# homeboard29.net
KiCad netlist of a schematic drawn in EAGLE
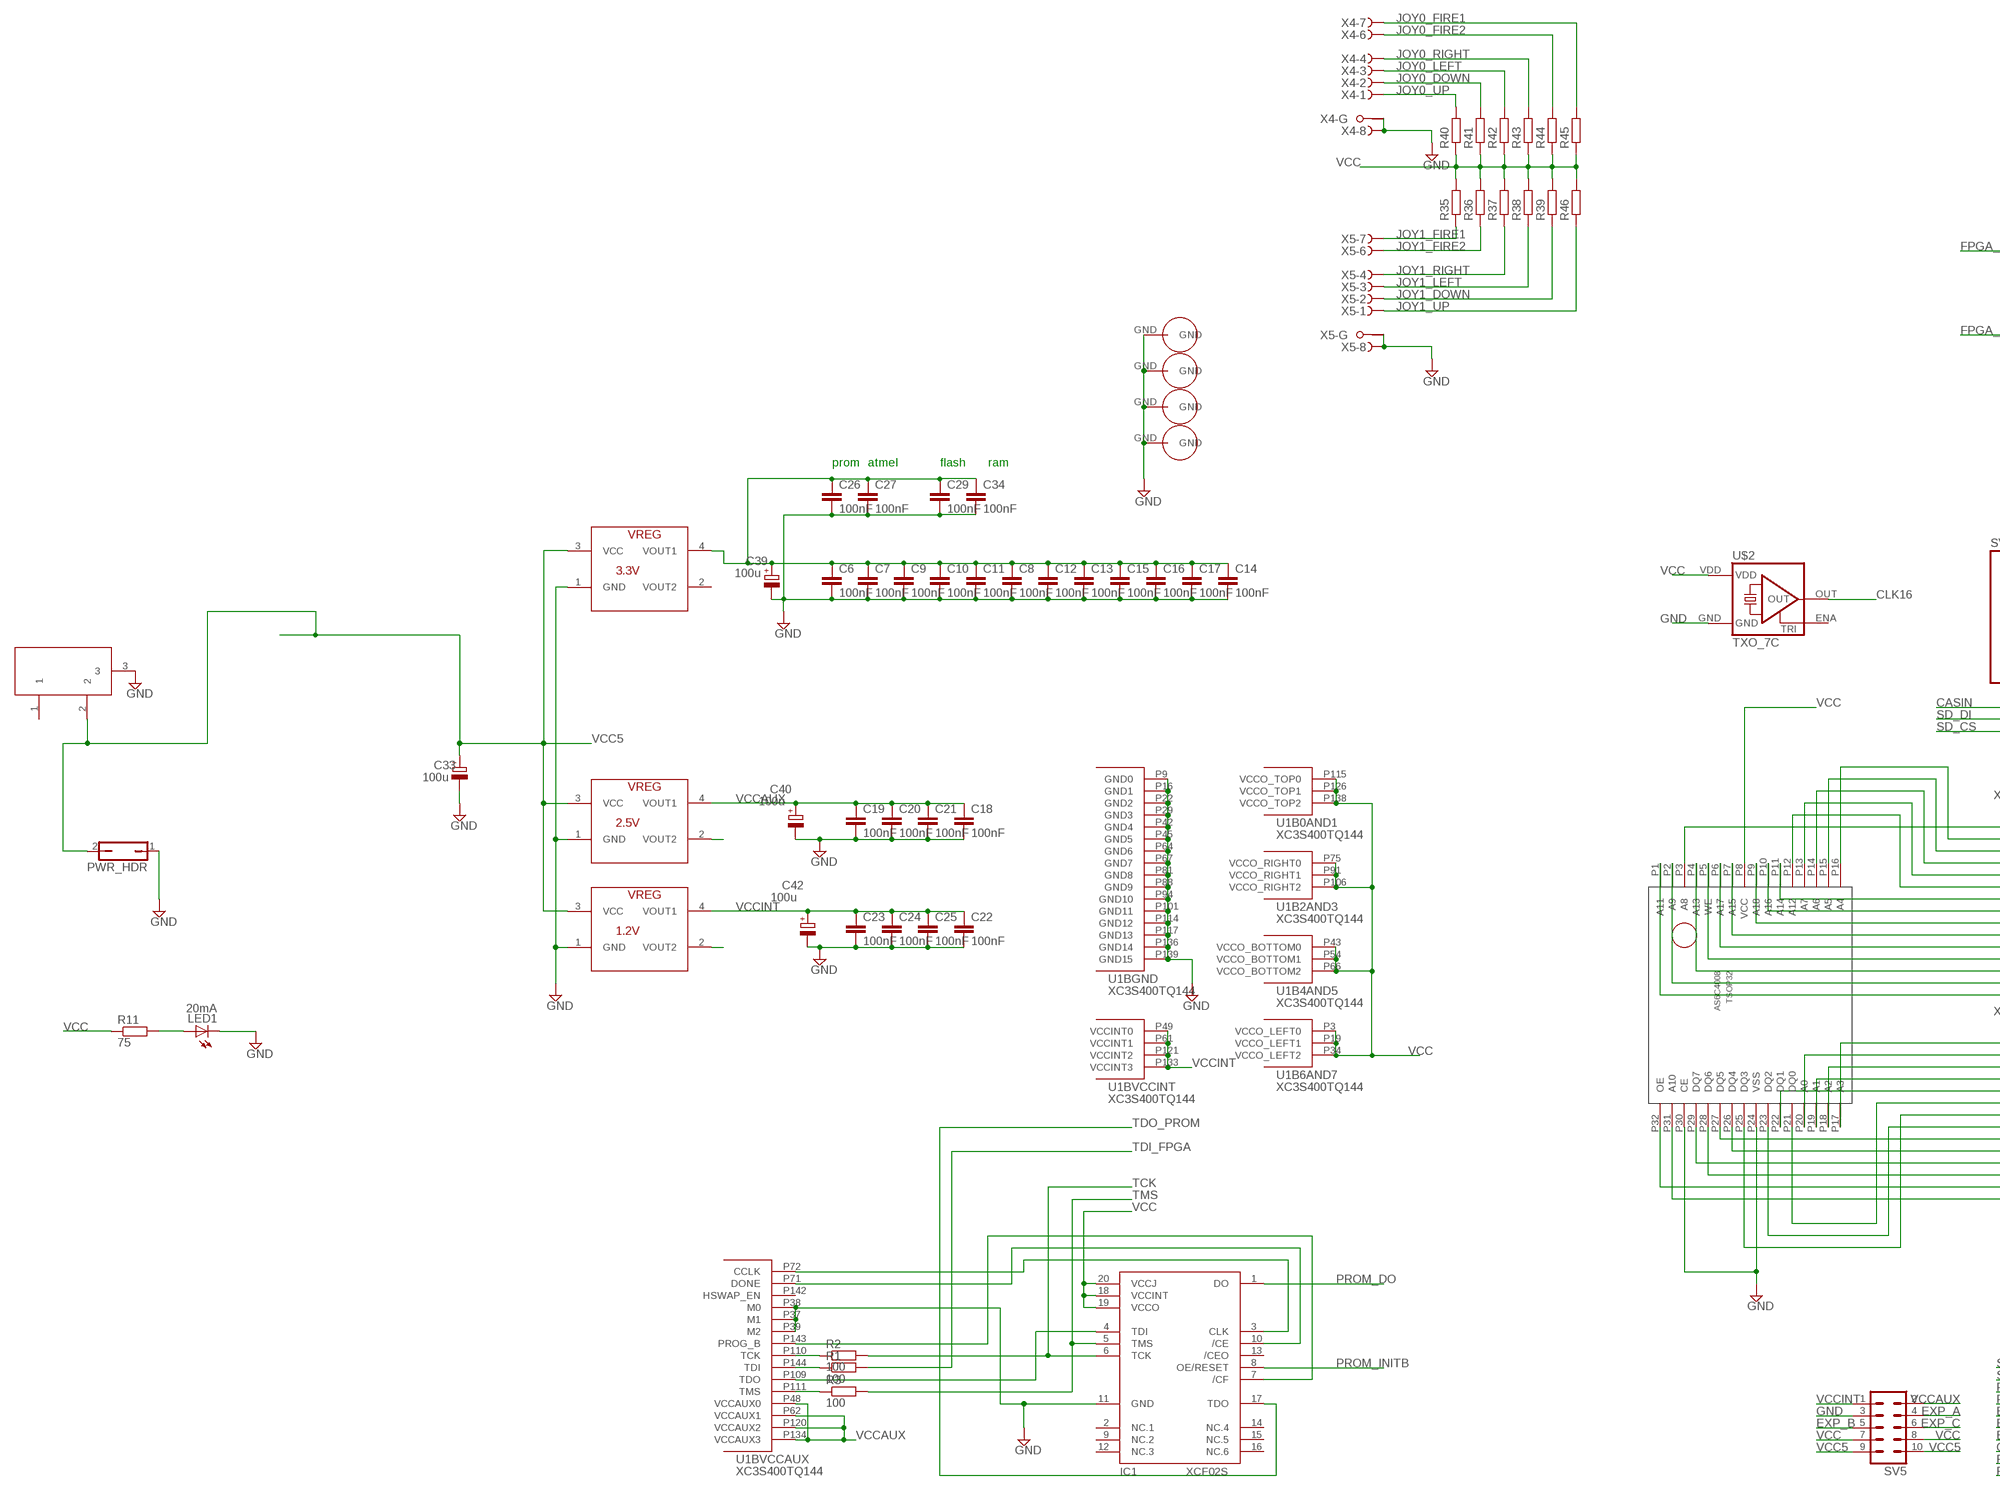
[diagram p0: schematic, sheet 1, part 1 of 3]
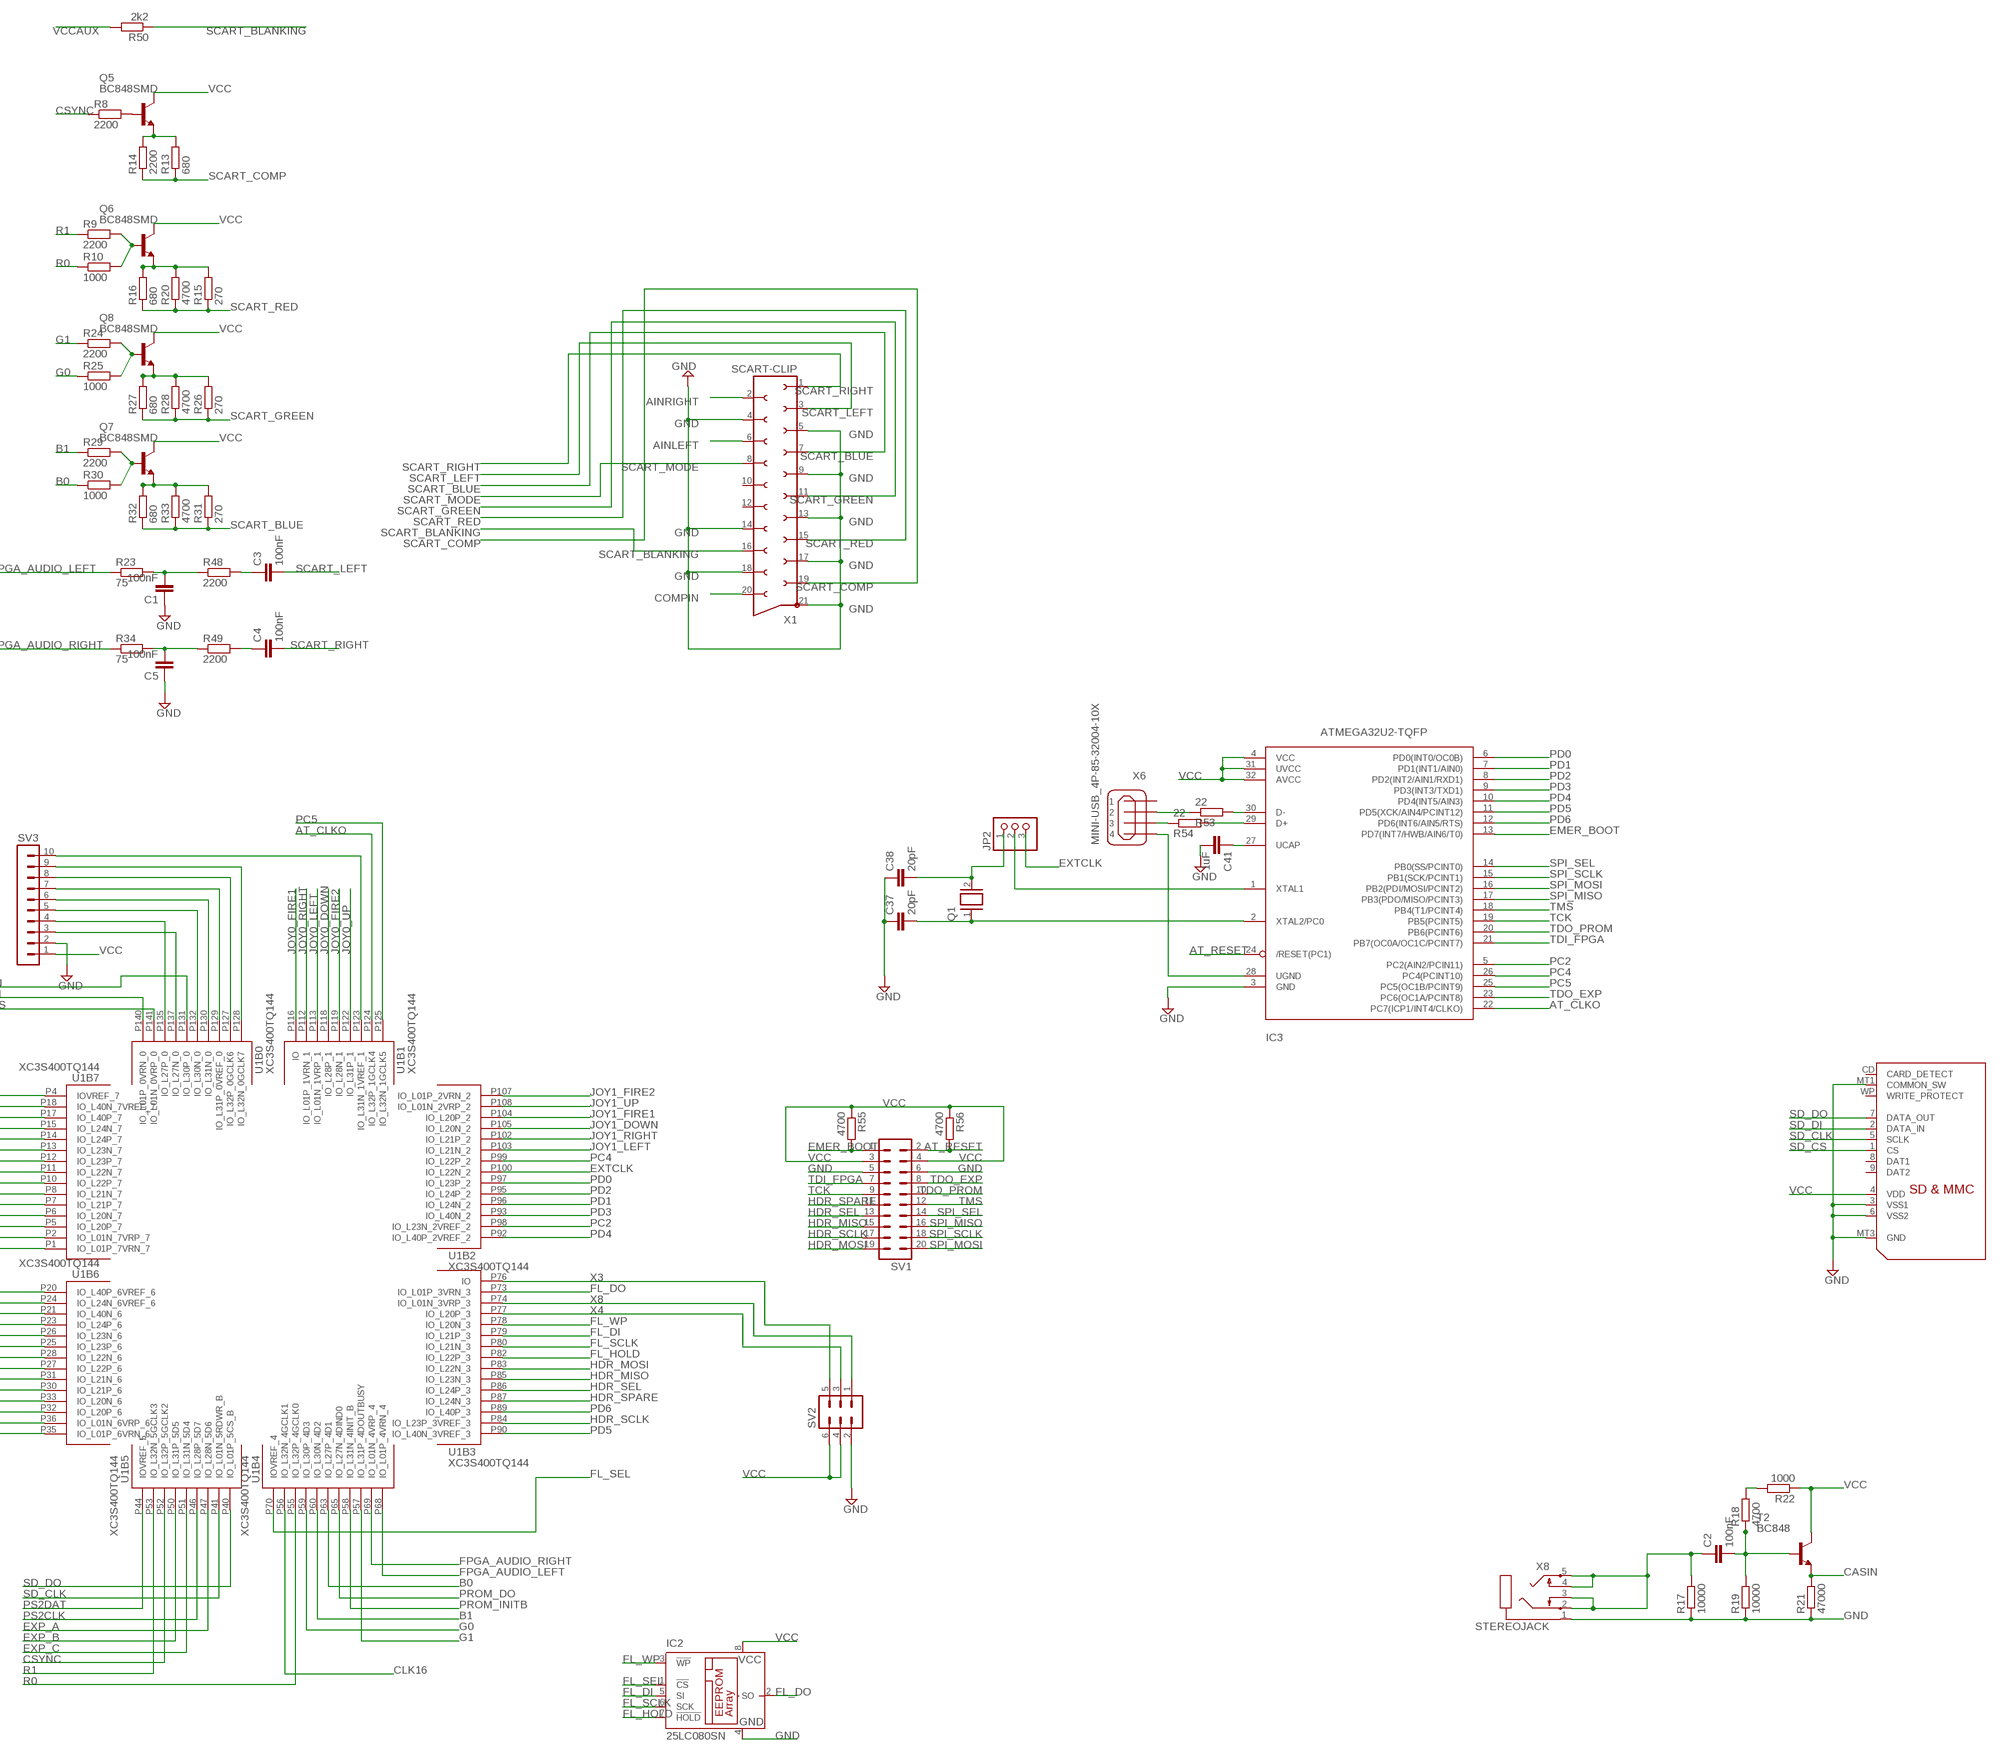
[diagram p1: schematic, sheet 1, part 2 of 3]
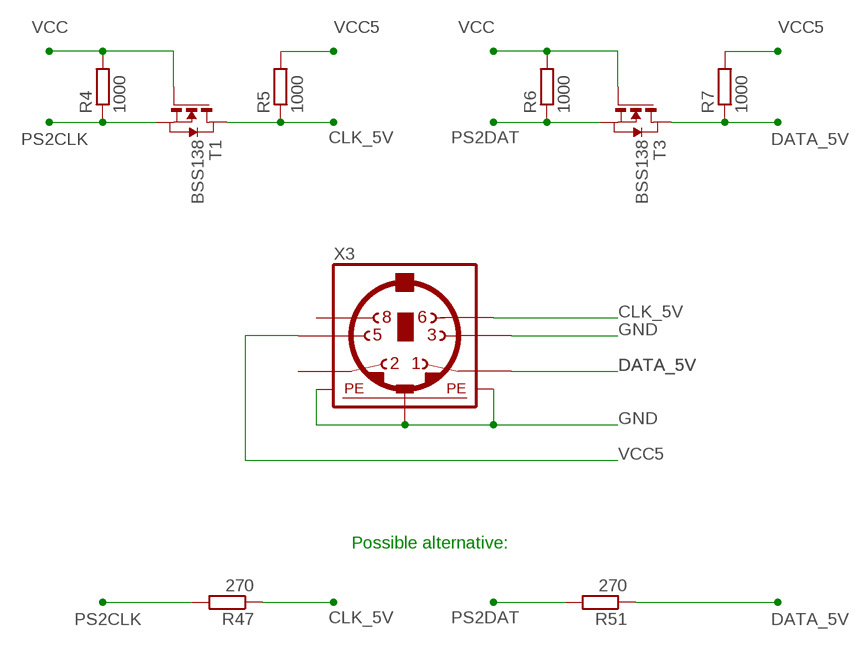
[diagram p2: schematic, sheet 1, part 3 of 3]

(export (version "E")
  (design (tool "Eeschema 10.0.6"))
  (components
    (comp (ref "C1")
      (value "100nF")
      (footprint "eagle-import:C0603")
      (libsource (lib "eagle-import") (part "resistor_C-EUC0603"))
    )
    (comp (ref "C2")
      (value "100nF")
      (footprint "eagle-import:C0603")
      (libsource (lib "eagle-import") (part "resistor_C-EUC0603"))
    )
    (comp (ref "C3")
      (value "100nF")
      (footprint "eagle-import:C0603")
      (libsource (lib "eagle-import") (part "resistor_C-EUC0603"))
    )
    (comp (ref "C4")
      (value "100nF")
      (footprint "eagle-import:C0603")
      (libsource (lib "eagle-import") (part "resistor_C-EUC0603"))
    )
    (comp (ref "C5")
      (value "100nF")
      (footprint "eagle-import:C0603")
      (libsource (lib "eagle-import") (part "resistor_C-EUC0603"))
    )
    (comp (ref "C6")
      (value "100nF")
      (footprint "eagle-import:C0603")
      (libsource (lib "eagle-import") (part "C-EUC0603"))
    )
    (comp (ref "C7")
      (value "100nF")
      (footprint "eagle-import:C0603")
      (libsource (lib "eagle-import") (part "C-EUC0603"))
    )
    (comp (ref "C8")
      (value "100nF")
      (footprint "eagle-import:C0603")
      (libsource (lib "eagle-import") (part "C-EUC0603"))
    )
    (comp (ref "C9")
      (value "100nF")
      (footprint "eagle-import:C0603")
      (libsource (lib "eagle-import") (part "C-EUC0603"))
    )
    (comp (ref "C10")
      (value "100nF")
      (footprint "eagle-import:C0603")
      (libsource (lib "eagle-import") (part "C-EUC0603"))
    )
    (comp (ref "C11")
      (value "100nF")
      (footprint "eagle-import:C0603")
      (libsource (lib "eagle-import") (part "C-EUC0603"))
    )
    (comp (ref "C12")
      (value "100nF")
      (footprint "eagle-import:C0603")
      (libsource (lib "eagle-import") (part "C-EUC0603"))
    )
    (comp (ref "C13")
      (value "100nF")
      (footprint "eagle-import:C0603")
      (libsource (lib "eagle-import") (part "C-EUC0603"))
    )
    (comp (ref "C14")
      (value "100nF")
      (footprint "eagle-import:C0603")
      (libsource (lib "eagle-import") (part "C-EUC0603"))
    )
    (comp (ref "C15")
      (value "100nF")
      (footprint "eagle-import:C0603")
      (libsource (lib "eagle-import") (part "C-EUC0603"))
    )
    (comp (ref "C16")
      (value "100nF")
      (footprint "eagle-import:C0603")
      (libsource (lib "eagle-import") (part "C-EUC0603"))
    )
    (comp (ref "C17")
      (value "100nF")
      (footprint "eagle-import:C0603")
      (libsource (lib "eagle-import") (part "C-EUC0603"))
    )
    (comp (ref "C18")
      (value "100nF")
      (footprint "eagle-import:C0603")
      (libsource (lib "eagle-import") (part "C-EUC0603"))
    )
    (comp (ref "C19")
      (value "100nF")
      (footprint "eagle-import:C0603")
      (libsource (lib "eagle-import") (part "C-EUC0603"))
    )
    (comp (ref "C20")
      (value "100nF")
      (footprint "eagle-import:C0603")
      (libsource (lib "eagle-import") (part "C-EUC0603"))
    )
    (comp (ref "C21")
      (value "100nF")
      (footprint "eagle-import:C0603")
      (libsource (lib "eagle-import") (part "C-EUC0603"))
    )
    (comp (ref "C22")
      (value "100nF")
      (footprint "eagle-import:C0603")
      (libsource (lib "eagle-import") (part "C-EUC0603"))
    )
    (comp (ref "C23")
      (value "100nF")
      (footprint "eagle-import:C0603")
      (libsource (lib "eagle-import") (part "C-EUC0603"))
    )
    (comp (ref "C24")
      (value "100nF")
      (footprint "eagle-import:C0603")
      (libsource (lib "eagle-import") (part "C-EUC0603"))
    )
    (comp (ref "C25")
      (value "100nF")
      (footprint "eagle-import:C0603")
      (libsource (lib "eagle-import") (part "C-EUC0603"))
    )
    (comp (ref "C26")
      (value "100nF")
      (footprint "eagle-import:C0603")
      (libsource (lib "eagle-import") (part "C-EUC0603"))
    )
    (comp (ref "C27")
      (value "100nF")
      (footprint "eagle-import:C0603")
      (libsource (lib "eagle-import") (part "C-EUC0603"))
    )
    (comp (ref "C29")
      (value "100nF")
      (footprint "eagle-import:C0603")
      (libsource (lib "eagle-import") (part "C-EUC0603"))
    )
    (comp (ref "C33")
      (value "100u")
      (footprint "eagle-import:PANASONIC_D")
      (libsource (lib "eagle-import") (part "CPOL-EUD"))
    )
    (comp (ref "C34")
      (value "100nF")
      (footprint "eagle-import:C0603")
      (libsource (lib "eagle-import") (part "C-EUC0603"))
    )
    (comp (ref "C37")
      (value "20pF")
      (footprint "eagle-import:C0805")
      (libsource (lib "eagle-import") (part "C-EUC0805"))
    )
    (comp (ref "C38")
      (value "20pF")
      (footprint "eagle-import:C0805")
      (libsource (lib "eagle-import") (part "C-EUC0805"))
    )
    (comp (ref "C39")
      (value "100u")
      (footprint "eagle-import:PANASONIC_D")
      (libsource (lib "eagle-import") (part "CPOL-EUD"))
    )
    (comp (ref "C40")
      (value "100u")
      (footprint "eagle-import:PANASONIC_D")
      (libsource (lib "eagle-import") (part "CPOL-EUD"))
    )
    (comp (ref "C41")
      (value "1uF")
      (footprint "eagle-import:C0805")
      (libsource (lib "eagle-import") (part "C-EUC0805"))
    )
    (comp (ref "C42")
      (value "100u")
      (footprint "eagle-import:PANASONIC_D")
      (libsource (lib "eagle-import") (part "CPOL-EUD"))
    )
    (comp (ref "IC1")
      (value "XCF02S")
      (footprint "eagle-import:VO20")
      (libsource (lib "eagle-import") (part "XCF02S"))
    )
    (comp (ref "IC2")
      (value "25LC080SN")
      (footprint "eagle-import:SO-08")
      (fields (field (name "MF") "MICROCHIP") (field (name "MPN") "25LC080/SN"))
      (libsource (lib "eagle-import") (part "25SNLC080"))
    )
    (comp (ref "IC3")
      (value "ATMEGA32U2-TQFP")
      (footprint "eagle-import:TQFP32-08")
      (libsource (lib "eagle-import") (part "ATMEGA32U2-TQFP"))
    )
    (comp (ref "JP2")
      (value "PINHD-1X3")
      (footprint "eagle-import:1X03")
      (libsource (lib "eagle-import") (part "PINHD-1X3"))
    )
    (comp (ref "LED1")
      (value "20mA")
      (footprint "eagle-import:CHIPLED_0805")
      (libsource (lib "eagle-import") (part "LEDCHIPLED_0805"))
    )
    (comp (ref "PWR_HDR")
      (value "JP1Q")
      (footprint "eagle-import:JP1")
      (libsource (lib "eagle-import") (part "JP1Q"))
    )
    (comp (ref "Q1")
      (value "XTAL/S")
      (footprint "eagle-import:QS")
      (libsource (lib "eagle-import") (part "XTAL/S"))
    )
    (comp (ref "Q5")
      (value "BC848SMD")
      (footprint "eagle-import:SOT23")
      (libsource (lib "eagle-import") (part "BC848SMD"))
    )
    (comp (ref "Q6")
      (value "BC848SMD")
      (footprint "eagle-import:SOT23")
      (libsource (lib "eagle-import") (part "BC848SMD"))
    )
    (comp (ref "Q7")
      (value "BC848SMD")
      (footprint "eagle-import:SOT23")
      (libsource (lib "eagle-import") (part "BC848SMD"))
    )
    (comp (ref "Q8")
      (value "BC848SMD")
      (footprint "eagle-import:SOT23")
      (libsource (lib "eagle-import") (part "BC848SMD"))
    )
    (comp (ref "R1")
      (value "100")
      (footprint "eagle-import:R0805")
      (libsource (lib "eagle-import") (part "R-EU_R0805"))
    )
    (comp (ref "R2")
      (value "100")
      (footprint "eagle-import:R0805")
      (libsource (lib "eagle-import") (part "R-EU_R0805"))
    )
    (comp (ref "R3")
      (value "100")
      (footprint "eagle-import:R0805")
      (libsource (lib "eagle-import") (part "R-EU_R0805"))
    )
    (comp (ref "R4")
      (value "1000")
      (footprint "eagle-import:R0805")
      (libsource (lib "eagle-import") (part "R-EU_R0805"))
    )
    (comp (ref "R5")
      (value "1000")
      (footprint "eagle-import:R0805")
      (libsource (lib "eagle-import") (part "R-EU_R0805"))
    )
    (comp (ref "R6")
      (value "1000")
      (footprint "eagle-import:R0805")
      (libsource (lib "eagle-import") (part "R-EU_R0805"))
    )
    (comp (ref "R7")
      (value "1000")
      (footprint "eagle-import:R0805")
      (libsource (lib "eagle-import") (part "R-EU_R0805"))
    )
    (comp (ref "R8")
      (value "2200")
      (footprint "eagle-import:R0805")
      (libsource (lib "eagle-import") (part "R-EU_R0805"))
    )
    (comp (ref "R9")
      (value "2200")
      (footprint "eagle-import:R0805")
      (libsource (lib "eagle-import") (part "R-EU_R0805"))
    )
    (comp (ref "R10")
      (value "1000")
      (footprint "eagle-import:R0805")
      (libsource (lib "eagle-import") (part "R-EU_R0805"))
    )
    (comp (ref "R11")
      (value "75")
      (footprint "eagle-import:M0805")
      (libsource (lib "eagle-import") (part "resistor_R-EU_M0805"))
    )
    (comp (ref "R13")
      (value "680")
      (footprint "eagle-import:R0805")
      (libsource (lib "eagle-import") (part "R-EU_R0805"))
    )
    (comp (ref "R14")
      (value "2200")
      (footprint "eagle-import:R0805")
      (libsource (lib "eagle-import") (part "R-EU_R0805"))
    )
    (comp (ref "R15")
      (value "270")
      (footprint "eagle-import:R0805")
      (libsource (lib "eagle-import") (part "R-EU_R0805"))
    )
    (comp (ref "R16")
      (value "680")
      (footprint "eagle-import:R0805")
      (libsource (lib "eagle-import") (part "R-EU_R0805"))
    )
    (comp (ref "R17")
      (value "10000")
      (footprint "eagle-import:R0805")
      (libsource (lib "eagle-import") (part "R-EU_R0805"))
    )
    (comp (ref "R18")
      (value "4700")
      (footprint "eagle-import:R0805")
      (libsource (lib "eagle-import") (part "R-EU_R0805"))
    )
    (comp (ref "R19")
      (value "10000")
      (footprint "eagle-import:R0805")
      (libsource (lib "eagle-import") (part "R-EU_R0805"))
    )
    (comp (ref "R20")
      (value "4700")
      (footprint "eagle-import:R0805")
      (libsource (lib "eagle-import") (part "R-EU_R0805"))
    )
    (comp (ref "R21")
      (value "47000")
      (footprint "eagle-import:R0805")
      (libsource (lib "eagle-import") (part "R-EU_R0805"))
    )
    (comp (ref "R22")
      (value "1000")
      (footprint "eagle-import:R0805")
      (libsource (lib "eagle-import") (part "R-EU_R0805"))
    )
    (comp (ref "R23")
      (value "75")
      (footprint "eagle-import:M0805")
      (libsource (lib "eagle-import") (part "resistor_R-EU_M0805"))
    )
    (comp (ref "R24")
      (value "2200")
      (footprint "eagle-import:R0805")
      (libsource (lib "eagle-import") (part "R-EU_R0805"))
    )
    (comp (ref "R25")
      (value "1000")
      (footprint "eagle-import:R0805")
      (libsource (lib "eagle-import") (part "R-EU_R0805"))
    )
    (comp (ref "R26")
      (value "270")
      (footprint "eagle-import:R0805")
      (libsource (lib "eagle-import") (part "R-EU_R0805"))
    )
    (comp (ref "R27")
      (value "680")
      (footprint "eagle-import:R0805")
      (libsource (lib "eagle-import") (part "R-EU_R0805"))
    )
    (comp (ref "R28")
      (value "4700")
      (footprint "eagle-import:R0805")
      (libsource (lib "eagle-import") (part "R-EU_R0805"))
    )
    (comp (ref "R29")
      (value "2200")
      (footprint "eagle-import:R0805")
      (libsource (lib "eagle-import") (part "R-EU_R0805"))
    )
    (comp (ref "R30")
      (value "1000")
      (footprint "eagle-import:R0805")
      (libsource (lib "eagle-import") (part "R-EU_R0805"))
    )
    (comp (ref "R31")
      (value "270")
      (footprint "eagle-import:R0805")
      (libsource (lib "eagle-import") (part "R-EU_R0805"))
    )
    (comp (ref "R32")
      (value "680")
      (footprint "eagle-import:R0805")
      (libsource (lib "eagle-import") (part "R-EU_R0805"))
    )
    (comp (ref "R33")
      (value "4700")
      (footprint "eagle-import:R0805")
      (libsource (lib "eagle-import") (part "R-EU_R0805"))
    )
    (comp (ref "R34")
      (value "75")
      (footprint "eagle-import:M0805")
      (libsource (lib "eagle-import") (part "resistor_R-EU_M0805"))
    )
    (comp (ref "R35")
      (value "R-EU_M0805")
      (footprint "eagle-import:M0805")
      (libsource (lib "eagle-import") (part "resistor_R-EU_M0805"))
    )
    (comp (ref "R36")
      (value "R-EU_M0805")
      (footprint "eagle-import:M0805")
      (libsource (lib "eagle-import") (part "resistor_R-EU_M0805"))
    )
    (comp (ref "R37")
      (value "R-EU_M0805")
      (footprint "eagle-import:M0805")
      (libsource (lib "eagle-import") (part "resistor_R-EU_M0805"))
    )
    (comp (ref "R38")
      (value "R-EU_M0805")
      (footprint "eagle-import:M0805")
      (libsource (lib "eagle-import") (part "resistor_R-EU_M0805"))
    )
    (comp (ref "R39")
      (value "R-EU_M0805")
      (footprint "eagle-import:M0805")
      (libsource (lib "eagle-import") (part "resistor_R-EU_M0805"))
    )
    (comp (ref "R40")
      (value "R-EU_M0805")
      (footprint "eagle-import:M0805")
      (libsource (lib "eagle-import") (part "resistor_R-EU_M0805"))
    )
    (comp (ref "R41")
      (value "R-EU_M0805")
      (footprint "eagle-import:M0805")
      (libsource (lib "eagle-import") (part "resistor_R-EU_M0805"))
    )
    (comp (ref "R42")
      (value "R-EU_M0805")
      (footprint "eagle-import:M0805")
      (libsource (lib "eagle-import") (part "resistor_R-EU_M0805"))
    )
    (comp (ref "R43")
      (value "R-EU_M0805")
      (footprint "eagle-import:M0805")
      (libsource (lib "eagle-import") (part "resistor_R-EU_M0805"))
    )
    (comp (ref "R44")
      (value "R-EU_M0805")
      (footprint "eagle-import:M0805")
      (libsource (lib "eagle-import") (part "resistor_R-EU_M0805"))
    )
    (comp (ref "R45")
      (value "R-EU_M0805")
      (footprint "eagle-import:M0805")
      (libsource (lib "eagle-import") (part "resistor_R-EU_M0805"))
    )
    (comp (ref "R46")
      (value "R-EU_M0805")
      (footprint "eagle-import:M0805")
      (libsource (lib "eagle-import") (part "resistor_R-EU_M0805"))
    )
    (comp (ref "R47")
      (value "270")
      (footprint "eagle-import:R0805")
      (libsource (lib "eagle-import") (part "R-EU_R0805"))
    )
    (comp (ref "R48")
      (value "2200")
      (footprint "eagle-import:M0805")
      (libsource (lib "eagle-import") (part "resistor_R-EU_M0805"))
    )
    (comp (ref "R49")
      (value "2200")
      (footprint "eagle-import:M0805")
      (libsource (lib "eagle-import") (part "resistor_R-EU_M0805"))
    )
    (comp (ref "R50")
      (value "2k2")
      (footprint "eagle-import:M0805")
      (libsource (lib "eagle-import") (part "resistor_R-EU_M0805"))
    )
    (comp (ref "R51")
      (value "270")
      (footprint "eagle-import:R0805")
      (libsource (lib "eagle-import") (part "R-EU_R0805"))
    )
    (comp (ref "R53")
      (value "22")
      (footprint "eagle-import:R0805")
      (libsource (lib "eagle-import") (part "R-EU_R0805"))
    )
    (comp (ref "R54")
      (value "22")
      (footprint "eagle-import:R0805")
      (libsource (lib "eagle-import") (part "R-EU_R0805"))
    )
    (comp (ref "R55")
      (value "4700")
      (footprint "eagle-import:R0805")
      (libsource (lib "eagle-import") (part "R-EU_R0805"))
    )
    (comp (ref "R56")
      (value "4700")
      (footprint "eagle-import:R0805")
      (libsource (lib "eagle-import") (part "R-EU_R0805"))
    )
    (comp (ref "REG1.2")
      (value "1.2V")
      (footprint "eagle-import:SOT223")
      (libsource (lib "eagle-import") (part "NX1117"))
    )
    (comp (ref "REG2.5")
      (value "2.5V")
      (footprint "eagle-import:SOT223")
      (libsource (lib "eagle-import") (part "NX1117"))
    )
    (comp (ref "REG3.3")
      (value "3.3V")
      (footprint "eagle-import:SOT223")
      (libsource (lib "eagle-import") (part "NX1117"))
    )
    (comp (ref "SV1")
      (value "MA10-2")
      (footprint "eagle-import:MA10-2")
      (fields (field (name "OC_FARNELL") "unknown") (field (name "OC_NEWARK") "unknown"))
      (libsource (lib "eagle-import") (part "MA10-2"))
    )
    (comp (ref "SV2")
      (value "MA03-2")
      (footprint "eagle-import:MA03-2")
      (libsource (lib "eagle-import") (part "MA03-2"))
    )
    (comp (ref "SV3")
      (value "MA10-1")
      (footprint "eagle-import:MA10-1")
      (libsource (lib "eagle-import") (part "MA10-1"))
    )
    (comp (ref "SV5")
      (value "MA05-2")
      (footprint "eagle-import:MA05-2")
      (libsource (lib "eagle-import") (part "MA05-2"))
    )
    (comp (ref "T1")
      (value "BSS138")
      (footprint "eagle-import:SOT-23")
      (libsource (lib "eagle-import") (part "NMOSSOT23"))
    )
    (comp (ref "T2")
      (value "BC848")
      (footprint "eagle-import:SOT23")
      (libsource (lib "eagle-import") (part "BC848"))
    )
    (comp (ref "T3")
      (value "BSS138")
      (footprint "eagle-import:SOT-23")
      (libsource (lib "eagle-import") (part "NMOSSOT23"))
    )
    (comp (ref "U$1")
      (value "GNDHOLE")
      (footprint "eagle-import:GNDHOLE")
      (libsource (lib "eagle-import") (part "GNDHOLE"))
    )
    (comp (ref "U$2")
      (value "TXO_7C")
      (footprint "eagle-import:OSC_7C")
      (libsource (lib "eagle-import") (part "TXO_7C"))
    )
    (comp (ref "U$3")
      (value "SDMMCNOHOLE")
      (footprint "eagle-import:SDCARD-NOHOLE")
      (libsource (lib "eagle-import") (part "SDMMCNOHOLE"))
    )
    (comp (ref "U$6")
      (value "AS6C4008")
      (footprint "eagle-import:TSOP32")
      (libsource (lib "eagle-import") (part "AS6C4008"))
    )
    (comp (ref "U$7")
      (value "GNDHOLE")
      (footprint "eagle-import:GNDHOLE")
      (libsource (lib "eagle-import") (part "GNDHOLE"))
    )
    (comp (ref "U$8")
      (value "GNDHOLE")
      (footprint "eagle-import:GNDHOLE")
      (libsource (lib "eagle-import") (part "GNDHOLE"))
    )
    (comp (ref "U$9")
      (value "GNDHOLE")
      (footprint "eagle-import:GNDHOLE")
      (libsource (lib "eagle-import") (part "GNDHOLE"))
    )
    (comp (ref "U1")
      (value "XC3S400TQ144")
      (footprint "eagle-import:TQ144")
      (libsource (lib "eagle-import") (part "XC3S400TQ144"))
    )
    (comp (ref "X1")
      (value "SCART-CLIP")
      (footprint "eagle-import:SCART-CLIP")
      (libsource (lib "eagle-import") (part "SCART-CLIP"))
    )
    (comp (ref "X3")
      (value "MINI_DIN_6")
      (footprint "eagle-import:M_DIN6")
      (libsource (lib "eagle-import") (part "MINI_DIN_6"))
    )
    (comp (ref "X4")
      (value "F09HPS")
      (footprint "eagle-import:F09HP")
      (libsource (lib "eagle-import") (part "F09HPS"))
    )
    (comp (ref "X5")
      (value "F09HPS")
      (footprint "eagle-import:F09HP")
      (libsource (lib "eagle-import") (part "F09HPS"))
    )
    (comp (ref "X6")
      (value "MINI-USB_4P-85-32004-10X")
      (footprint "eagle-import:85-32004-10X")
      (libsource (lib "eagle-import") (part "MINI-USB_4P-85-32004-10X"))
    )
    (comp (ref "X7")
      (value "DC21MMX")
      (footprint "eagle-import:DC-21MM")
      (libsource (lib "eagle-import") (part "DC21MMX"))
    )
    (comp (ref "X8")
      (value "STEREOJACK")
      (footprint "eagle-import:20-0137")
      (libsource (lib "eagle-import") (part "STEREOJACK"))
    )
  )
  (nets
    (net (code "1") (name "/1") (class "Default")
      (node (ref "X7") (pin "1") (pinfunction "1_1") (pintype "power_in"))
    )
    (net (code "2") (name "/AINLEFT") (class "Default")
      (node (ref "X1") (pin "6") (pinfunction "6_6") (pintype "passive"))
    )
    (net (code "3") (name "/AINRIGHT") (class "Default")
      (node (ref "X1") (pin "2") (pinfunction "2_2") (pintype "passive"))
    )
    (net (code "4") (name "/AT_CLKO") (class "Default")
      (node (ref "IC3") (pin "22") (pinfunction "PC7(ICP1/INT4/CLKO)_22") (pintype "bidirectional"))
      (node (ref "U1") (pin "P124") (pinfunction "IO_L32P_1GCLK4_P124") (pintype "bidirectional"))
    )
    (net (code "5") (name "/AT_RESET") (class "Default")
      (node (ref "IC3") (pin "24") (pinfunction "/RESET(PC1)_24") (pintype "bidirectional"))
      (node (ref "R56") (pin "2") (pinfunction "2_2") (pintype "passive"))
      (node (ref "SV1") (pin "2") (pinfunction "2_2") (pintype "passive"))
    )
    (net (code "6") (name "/B0") (class "Default")
      (node (ref "R30") (pin "1") (pinfunction "1_1") (pintype "passive"))
      (node (ref "U1") (pin "P63") (pinfunction "IO_L27P_4D1_P63") (pintype "bidirectional"))
    )
    (net (code "7") (name "/B1") (class "Default")
      (node (ref "R29") (pin "1") (pinfunction "1_1") (pintype "passive"))
      (node (ref "U1") (pin "P60") (pinfunction "IO_L30N_4D2_P60") (pintype "bidirectional"))
    )
    (net (code "8") (name "/CASIN") (class "Default")
      (node (ref "R21") (pin "2") (pinfunction "2_2") (pintype "passive"))
      (node (ref "T2") (pin "2") (pinfunction "E_2") (pintype "passive"))
      (node (ref "U1") (pin "P131") (pinfunction "IO_L30P_0_P131") (pintype "bidirectional"))
    )
    (net (code "9") (name "/CLK16") (class "Default")
      (node (ref "U$2") (pin "OUT") (pinfunction "OUT_OUT") (pintype "output"))
      (node (ref "U1") (pin "P56") (pinfunction "IO_L32N_4GCLK1_P56") (pintype "bidirectional"))
    )
    (net (code "10") (name "/CLK_5V") (class "Default")
      (node (ref "R47") (pin "1") (pinfunction "1_1") (pintype "passive"))
      (node (ref "R5") (pin "1") (pinfunction "1_1") (pintype "passive"))
      (node (ref "T1") (pin "1") (pinfunction "D_1") (pintype "passive"))
      (node (ref "X3") (pin "6") (pinfunction "6_6") (pintype "passive"))
    )
    (net (code "11") (name "/COMPIN") (class "Default")
      (node (ref "X1") (pin "20") (pinfunction "20_20") (pintype "passive"))
    )
    (net (code "12") (name "/CSYNC") (class "Default")
      (node (ref "R8") (pin "1") (pinfunction "1_1") (pintype "passive"))
      (node (ref "U1") (pin "P52") (pinfunction "IO_L32P_5GCLK2_P52") (pintype "bidirectional"))
    )
    (net (code "13") (name "/DATA_5V") (class "Default")
      (node (ref "R51") (pin "1") (pinfunction "1_1") (pintype "passive"))
      (node (ref "R7") (pin "1") (pinfunction "1_1") (pintype "passive"))
      (node (ref "T3") (pin "1") (pinfunction "D_1") (pintype "passive"))
      (node (ref "X3") (pin "1") (pinfunction "1_1") (pintype "passive"))
    )
    (net (code "14") (name "/EMER_BOOT") (class "Default")
      (node (ref "IC3") (pin "13") (pinfunction "PD7(INT7/HWB/AIN6/T0)_13") (pintype "bidirectional"))
      (node (ref "R55") (pin "2") (pinfunction "2_2") (pintype "passive"))
      (node (ref "SV1") (pin "1") (pinfunction "1_1") (pintype "passive"))
    )
    (net (code "15") (name "/EXP_A") (class "Default")
      (node (ref "SV5") (pin "4") (pinfunction "4_4") (pintype "passive"))
      (node (ref "U1") (pin "P47") (pinfunction "IO_L28N_5D6_P47") (pintype "bidirectional"))
    )
    (net (code "16") (name "/EXP_B") (class "Default")
      (node (ref "SV5") (pin "5") (pinfunction "5_5") (pintype "passive"))
      (node (ref "U1") (pin "P50") (pinfunction "IO_L31P_5D5_P50") (pintype "bidirectional"))
    )
    (net (code "17") (name "/EXP_C") (class "Default")
      (node (ref "SV5") (pin "6") (pinfunction "6_6") (pintype "passive"))
      (node (ref "U1") (pin "P51") (pinfunction "IO_L31N_5D4_P51") (pintype "bidirectional"))
    )
    (net (code "18") (name "/EXTCLK") (class "Default")
      (node (ref "JP2") (pin "3") (pinfunction "3_3") (pintype "passive"))
      (node (ref "U1") (pin "P100") (pinfunction "IO_L22N_2_P100") (pintype "bidirectional"))
    )
    (net (code "19") (name "/FL_DI") (class "Default")
      (node (ref "IC2") (pin "5") (pinfunction "SI_5") (pintype "input"))
      (node (ref "U1") (pin "P79") (pinfunction "IO_L21P_3_P79") (pintype "bidirectional"))
    )
    (net (code "20") (name "/FL_DO") (class "Default")
      (node (ref "IC2") (pin "2") (pinfunction "SO_2") (pintype "bidirectional"))
      (node (ref "U1") (pin "P73") (pinfunction "IO_L01P_3VRN_3_P73") (pintype "bidirectional"))
    )
    (net (code "21") (name "/FL_HOLD") (class "Default")
      (node (ref "IC2") (pin "7") (pinfunction "~{HOLD}_7") (pintype "input"))
      (node (ref "U1") (pin "P82") (pinfunction "IO_L22P_3_P82") (pintype "bidirectional"))
    )
    (net (code "22") (name "/FL_SCLK") (class "Default")
      (node (ref "IC2") (pin "6") (pinfunction "SCK_6") (pintype "input"))
      (node (ref "U1") (pin "P80") (pinfunction "IO_L21N_3_P80") (pintype "bidirectional"))
    )
    (net (code "23") (name "/FL_SEL") (class "Default")
      (node (ref "IC2") (pin "1") (pinfunction "~{CS}_1") (pintype "input"))
      (node (ref "U1") (pin "P70") (pinfunction "IOVREF_4_P70") (pintype "bidirectional"))
    )
    (net (code "24") (name "/FL_WP") (class "Default")
      (node (ref "IC2") (pin "3") (pinfunction "~{WP}_3") (pintype "input"))
      (node (ref "U1") (pin "P78") (pinfunction "IO_L20N_3_P78") (pintype "bidirectional"))
    )
    (net (code "25") (name "/FPGA_AUDIO_LEFT") (class "Default")
      (node (ref "R23") (pin "1") (pinfunction "1_1") (pintype "passive"))
      (node (ref "U1") (pin "P68") (pinfunction "IO_L01P_4VRN_4_P68") (pintype "bidirectional"))
    )
    (net (code "26") (name "/FPGA_AUDIO_RIGHT") (class "Default")
      (node (ref "R34") (pin "1") (pinfunction "1_1") (pintype "passive"))
      (node (ref "U1") (pin "P69") (pinfunction "IO_L01N_4VRP_4_P69") (pintype "bidirectional"))
    )
    (net (code "27") (name "/G0") (class "Default")
      (node (ref "R25") (pin "1") (pinfunction "1_1") (pintype "passive"))
      (node (ref "U1") (pin "P59") (pinfunction "IO_L30P_4D3_P59") (pintype "bidirectional"))
    )
    (net (code "28") (name "/G1") (class "Default")
      (node (ref "R24") (pin "1") (pinfunction "1_1") (pintype "passive"))
      (node (ref "U1") (pin "P57") (pinfunction "IO_L31P_4DOUTBUSY_P57") (pintype "bidirectional"))
    )
    (net (code "29") (name "/HDR_MISO") (class "Default")
      (node (ref "SV1") (pin "15") (pinfunction "15_15") (pintype "passive"))
      (node (ref "U1") (pin "P85") (pinfunction "IO_L23N_3_P85") (pintype "bidirectional"))
    )
    (net (code "30") (name "/HDR_MOSI") (class "Default")
      (node (ref "SV1") (pin "19") (pinfunction "19_19") (pintype "passive"))
      (node (ref "U1") (pin "P83") (pinfunction "IO_L22N_3_P83") (pintype "bidirectional"))
    )
    (net (code "31") (name "/HDR_SCLK") (class "Default")
      (node (ref "SV1") (pin "17") (pinfunction "17_17") (pintype "passive"))
      (node (ref "U1") (pin "P84") (pinfunction "IO_L23P_3VREF_3_P84") (pintype "bidirectional"))
    )
    (net (code "32") (name "/HDR_SEL") (class "Default")
      (node (ref "SV1") (pin "13") (pinfunction "13_13") (pintype "passive"))
      (node (ref "U1") (pin "P86") (pinfunction "IO_L24P_3_P86") (pintype "bidirectional"))
    )
    (net (code "33") (name "/HDR_SPARE") (class "Default")
      (node (ref "SV1") (pin "11") (pinfunction "11_11") (pintype "passive"))
      (node (ref "U1") (pin "P87") (pinfunction "IO_L24N_3_P87") (pintype "bidirectional"))
    )
    (net (code "34") (name "/JOY0_DOWN") (class "Default")
      (node (ref "R41") (pin "2") (pinfunction "2_2") (pintype "passive"))
      (node (ref "U1") (pin "P118") (pinfunction "IO_L28P_1_P118") (pintype "bidirectional"))
      (node (ref "X4") (pin "2") (pinfunction "F_2") (pintype "passive"))
    )
    (net (code "35") (name "/JOY0_FIRE1") (class "Default")
      (node (ref "R45") (pin "2") (pinfunction "2_2") (pintype "passive"))
      (node (ref "U1") (pin "P116") (pinfunction "IO_P116") (pintype "bidirectional"))
      (node (ref "X4") (pin "7") (pinfunction "F_7") (pintype "passive"))
    )
    (net (code "36") (name "/JOY0_FIRE2") (class "Default")
      (node (ref "R44") (pin "2") (pinfunction "2_2") (pintype "passive"))
      (node (ref "U1") (pin "P119") (pinfunction "IO_L28N_1_P119") (pintype "bidirectional"))
      (node (ref "X4") (pin "6") (pinfunction "F_6") (pintype "passive"))
    )
    (net (code "37") (name "/JOY0_LEFT") (class "Default")
      (node (ref "R42") (pin "2") (pinfunction "2_2") (pintype "passive"))
      (node (ref "U1") (pin "P113") (pinfunction "IO_L01N_1VRP_1_P113") (pintype "bidirectional"))
      (node (ref "X4") (pin "3") (pinfunction "F_3") (pintype "passive"))
    )
    (net (code "38") (name "/JOY0_RIGHT") (class "Default")
      (node (ref "R43") (pin "2") (pinfunction "2_2") (pintype "passive"))
      (node (ref "U1") (pin "P112") (pinfunction "IO_L01P_1VRN_1_P112") (pintype "bidirectional"))
      (node (ref "X4") (pin "4") (pinfunction "F_4") (pintype "passive"))
    )
    (net (code "39") (name "/JOY0_UP") (class "Default")
      (node (ref "R40") (pin "2") (pinfunction "2_2") (pintype "passive"))
      (node (ref "U1") (pin "P122") (pinfunction "IO_L31P_1_P122") (pintype "bidirectional"))
      (node (ref "X4") (pin "1") (pinfunction "F_1") (pintype "passive"))
    )
    (net (code "40") (name "/JOY1_DOWN") (class "Default")
      (node (ref "R39") (pin "1") (pinfunction "1_1") (pintype "passive"))
      (node (ref "U1") (pin "P105") (pinfunction "IO_L20N_2_P105") (pintype "bidirectional"))
      (node (ref "X5") (pin "2") (pinfunction "F_2") (pintype "passive"))
    )
    (net (code "41") (name "/JOY1_FIRE1") (class "Default")
      (node (ref "R35") (pin "1") (pinfunction "1_1") (pintype "passive"))
      (node (ref "U1") (pin "P104") (pinfunction "IO_L20P_2_P104") (pintype "bidirectional"))
      (node (ref "X5") (pin "7") (pinfunction "F_7") (pintype "passive"))
    )
    (net (code "42") (name "/JOY1_FIRE2") (class "Default")
      (node (ref "R36") (pin "1") (pinfunction "1_1") (pintype "passive"))
      (node (ref "U1") (pin "P107") (pinfunction "IO_L01P_2VRN_2_P107") (pintype "bidirectional"))
      (node (ref "X5") (pin "6") (pinfunction "F_6") (pintype "passive"))
    )
    (net (code "43") (name "/JOY1_LEFT") (class "Default")
      (node (ref "R38") (pin "1") (pinfunction "1_1") (pintype "passive"))
      (node (ref "U1") (pin "P103") (pinfunction "IO_L21N_2_P103") (pintype "bidirectional"))
      (node (ref "X5") (pin "3") (pinfunction "F_3") (pintype "passive"))
    )
    (net (code "44") (name "/JOY1_RIGHT") (class "Default")
      (node (ref "R37") (pin "1") (pinfunction "1_1") (pintype "passive"))
      (node (ref "U1") (pin "P102") (pinfunction "IO_L21P_2_P102") (pintype "bidirectional"))
      (node (ref "X5") (pin "4") (pinfunction "F_4") (pintype "passive"))
    )
    (net (code "45") (name "/JOY1_UP") (class "Default")
      (node (ref "R46") (pin "1") (pinfunction "1_1") (pintype "passive"))
      (node (ref "U1") (pin "P108") (pinfunction "IO_L01N_2VRP_2_P108") (pintype "bidirectional"))
      (node (ref "X5") (pin "1") (pinfunction "F_1") (pintype "passive"))
    )
    (net (code "46") (name "/PC2") (class "Default")
      (node (ref "IC3") (pin "5") (pinfunction "PC2(AIN2/PCIN11)_5") (pintype "bidirectional"))
      (node (ref "U1") (pin "P98") (pinfunction "IO_L23N_2VREF_2_P98") (pintype "bidirectional"))
    )
    (net (code "47") (name "/PC4") (class "Default")
      (node (ref "IC3") (pin "26") (pinfunction "PC4(PCINT10)_26") (pintype "bidirectional"))
      (node (ref "U1") (pin "P99") (pinfunction "IO_L22P_2_P99") (pintype "bidirectional"))
    )
    (net (code "48") (name "/PC5") (class "Default")
      (node (ref "IC3") (pin "25") (pinfunction "PC5(OC1B/PCINT9)_25") (pintype "bidirectional"))
      (node (ref "U1") (pin "P125") (pinfunction "IO_L32N_1GCLK5_P125") (pintype "bidirectional"))
    )
    (net (code "49") (name "/PD0") (class "Default")
      (node (ref "IC3") (pin "6") (pinfunction "PD0(INT0/OC0B)_6") (pintype "bidirectional"))
      (node (ref "U1") (pin "P97") (pinfunction "IO_L23P_2_P97") (pintype "bidirectional"))
    )
    (net (code "50") (name "/PD1") (class "Default")
      (node (ref "IC3") (pin "7") (pinfunction "PD1(INT1/AIN0)_7") (pintype "bidirectional"))
      (node (ref "U1") (pin "P96") (pinfunction "IO_L24N_2_P96") (pintype "bidirectional"))
    )
    (net (code "51") (name "/PD2") (class "Default")
      (node (ref "IC3") (pin "8") (pinfunction "PD2(INT2/AIN1/RXD1)_8") (pintype "bidirectional"))
      (node (ref "U1") (pin "P95") (pinfunction "IO_L24P_2_P95") (pintype "bidirectional"))
    )
    (net (code "52") (name "/PD3") (class "Default")
      (node (ref "IC3") (pin "9") (pinfunction "PD3(INT3/TXD1)_9") (pintype "bidirectional"))
      (node (ref "U1") (pin "P93") (pinfunction "IO_L40N_2_P93") (pintype "bidirectional"))
    )
    (net (code "53") (name "/PD4") (class "Default")
      (node (ref "IC3") (pin "10") (pinfunction "PD4(INT5/AIN3)_10") (pintype "bidirectional"))
      (node (ref "U1") (pin "P92") (pinfunction "IO_L40P_2VREF_2_P92") (pintype "bidirectional"))
    )
    (net (code "54") (name "/PD5") (class "Default")
      (node (ref "IC3") (pin "11") (pinfunction "PD5(XCK/AIN4/PCINT12)_11") (pintype "bidirectional"))
      (node (ref "U1") (pin "P90") (pinfunction "IO_L40N_3VREF_3_P90") (pintype "bidirectional"))
    )
    (net (code "55") (name "/PD6") (class "Default")
      (node (ref "IC3") (pin "12") (pinfunction "PD6(INT6/AIN5/RTS)_12") (pintype "bidirectional"))
      (node (ref "U1") (pin "P89") (pinfunction "IO_L40P_3_P89") (pintype "bidirectional"))
    )
    (net (code "56") (name "/PROM_DO") (class "Default")
      (node (ref "IC1") (pin "1") (pinfunction "DO_1") (pintype "bidirectional"))
      (node (ref "U1") (pin "P65") (pinfunction "IO_L27N_4DIND0_P65") (pintype "bidirectional"))
    )
    (net (code "57") (name "/PROM_INITB") (class "Default")
      (node (ref "IC1") (pin "8") (pinfunction "OE/RESET_8") (pintype "bidirectional"))
      (node (ref "U1") (pin "P58") (pinfunction "IO_L31N_4INIT_B_P58") (pintype "bidirectional"))
    )
    (net (code "58") (name "/PS2CLK") (class "Default")
      (node (ref "R4") (pin "1") (pinfunction "1_1") (pintype "passive"))
      (node (ref "R47") (pin "2") (pinfunction "2_2") (pintype "passive"))
      (node (ref "T1") (pin "2") (pinfunction "S_2") (pintype "passive"))
      (node (ref "U1") (pin "P46") (pinfunction "IO_L28P_5D7_P46") (pintype "bidirectional"))
    )
    (net (code "59") (name "/PS2DAT") (class "Default")
      (node (ref "R51") (pin "2") (pinfunction "2_2") (pintype "passive"))
      (node (ref "R6") (pin "1") (pinfunction "1_1") (pintype "passive"))
      (node (ref "T3") (pin "2") (pinfunction "S_2") (pintype "passive"))
      (node (ref "U1") (pin "P44") (pinfunction "IOVREF_5_P44") (pintype "bidirectional"))
    )
    (net (code "60") (name "/R0") (class "Default")
      (node (ref "R10") (pin "1") (pinfunction "1_1") (pintype "passive"))
      (node (ref "U1") (pin "P55") (pinfunction "IO_L32P_4GCLK0_P55") (pintype "bidirectional"))
    )
    (net (code "61") (name "/R1") (class "Default")
      (node (ref "R9") (pin "1") (pinfunction "1_1") (pintype "passive"))
      (node (ref "U1") (pin "P53") (pinfunction "IO_L32N_5GCLK3_P53") (pintype "bidirectional"))
    )
    (net (code "62") (name "/SCART_BLANKING") (class "Default")
      (node (ref "R50") (pin "1") (pinfunction "1_1") (pintype "passive"))
      (node (ref "X1") (pin "16") (pinfunction "16_16") (pintype "passive"))
    )
    (net (code "63") (name "/SCART_BLUE") (class "Default")
      (node (ref "R31") (pin "1") (pinfunction "1_1") (pintype "passive"))
      (node (ref "R32") (pin "1") (pinfunction "1_1") (pintype "passive"))
      (node (ref "R33") (pin "1") (pinfunction "1_1") (pintype "passive"))
      (node (ref "X1") (pin "7") (pinfunction "7_7") (pintype "passive"))
    )
    (net (code "64") (name "/SCART_COMP") (class "Default")
      (node (ref "R13") (pin "1") (pinfunction "1_1") (pintype "passive"))
      (node (ref "R14") (pin "1") (pinfunction "1_1") (pintype "passive"))
      (node (ref "X1") (pin "19") (pinfunction "19_19") (pintype "passive"))
    )
    (net (code "65") (name "/SCART_GREEN") (class "Default")
      (node (ref "R26") (pin "1") (pinfunction "1_1") (pintype "passive"))
      (node (ref "R27") (pin "1") (pinfunction "1_1") (pintype "passive"))
      (node (ref "R28") (pin "1") (pinfunction "1_1") (pintype "passive"))
      (node (ref "X1") (pin "11") (pinfunction "11_11") (pintype "passive"))
    )
    (net (code "66") (name "/SCART_LEFT") (class "Default")
      (node (ref "C3") (pin "2") (pinfunction "2_2") (pintype "passive"))
      (node (ref "X1") (pin "3") (pinfunction "3_3") (pintype "passive"))
    )
    (net (code "67") (name "/SCART_MODE") (class "Default")
      (node (ref "X1") (pin "8") (pinfunction "8_8") (pintype "passive"))
    )
    (net (code "68") (name "/SCART_RED") (class "Default")
      (node (ref "R15") (pin "1") (pinfunction "1_1") (pintype "passive"))
      (node (ref "R16") (pin "1") (pinfunction "1_1") (pintype "passive"))
      (node (ref "R20") (pin "1") (pinfunction "1_1") (pintype "passive"))
      (node (ref "X1") (pin "15") (pinfunction "15_15") (pintype "passive"))
    )
    (net (code "69") (name "/SCART_RIGHT") (class "Default")
      (node (ref "C4") (pin "2") (pinfunction "2_2") (pintype "passive"))
      (node (ref "X1") (pin "1") (pinfunction "1_1") (pintype "passive"))
    )
    (net (code "70") (name "/SD_CLK") (class "Default")
      (node (ref "U$3") (pin "5") (pinfunction "SCLK_5") (pintype "input"))
      (node (ref "U1") (pin "P41") (pinfunction "IO_L01N_5RDWR_B_P41") (pintype "bidirectional"))
    )
    (net (code "71") (name "/SD_CS") (class "Default")
      (node (ref "U$3") (pin "1") (pinfunction "CS_1") (pintype "input"))
      (node (ref "U1") (pin "P141") (pinfunction "IO_L01N_0VRP_0_P141") (pintype "bidirectional"))
    )
    (net (code "72") (name "/SD_DI") (class "Default")
      (node (ref "U$3") (pin "2") (pinfunction "DATA_IN_2") (pintype "input"))
      (node (ref "U1") (pin "P140") (pinfunction "IO_L01P_0VRN_0_P140") (pintype "bidirectional"))
    )
    (net (code "73") (name "/SD_DO") (class "Default")
      (node (ref "U$3") (pin "7") (pinfunction "DATA_OUT_7") (pintype "output"))
      (node (ref "U1") (pin "P40") (pinfunction "IO_L01P_5CS_B_P40") (pintype "bidirectional"))
    )
    (net (code "74") (name "/SPI_MISO") (class "Default")
      (node (ref "IC3") (pin "17") (pinfunction "PB3(PDO/MISO/PCINT3)_17") (pintype "bidirectional"))
      (node (ref "SV1") (pin "16") (pinfunction "16_16") (pintype "passive"))
    )
    (net (code "75") (name "/SPI_MOSI") (class "Default")
      (node (ref "IC3") (pin "16") (pinfunction "PB2(PDI/MOSI/PCINT2)_16") (pintype "bidirectional"))
      (node (ref "SV1") (pin "20") (pinfunction "20_20") (pintype "passive"))
    )
    (net (code "76") (name "/SPI_SCLK") (class "Default")
      (node (ref "IC3") (pin "15") (pinfunction "PB1(SCK/PCINT1)_15") (pintype "bidirectional"))
      (node (ref "SV1") (pin "18") (pinfunction "18_18") (pintype "passive"))
    )
    (net (code "77") (name "/SPI_SEL") (class "Default")
      (node (ref "IC3") (pin "14") (pinfunction "PB0(SS/PCINT0)_14") (pintype "bidirectional"))
      (node (ref "SV1") (pin "14") (pinfunction "14_14") (pintype "passive"))
    )
    (net (code "78") (name "/TCK") (class "Default")
      (node (ref "IC1") (pin "6") (pinfunction "TCK_6") (pintype "bidirectional"))
      (node (ref "IC3") (pin "19") (pinfunction "PB5(PCINT5)_19") (pintype "bidirectional"))
      (node (ref "R2") (pin "2") (pinfunction "2_2") (pintype "passive"))
      (node (ref "SV1") (pin "9") (pinfunction "9_9") (pintype "passive"))
    )
    (net (code "79") (name "/TDI_FPGA") (class "Default")
      (node (ref "IC3") (pin "21") (pinfunction "PB7(OC0A/OC1C/PCINT7)_21") (pintype "bidirectional"))
      (node (ref "R1") (pin "2") (pinfunction "2_2") (pintype "passive"))
      (node (ref "SV1") (pin "7") (pinfunction "7_7") (pintype "passive"))
    )
    (net (code "80") (name "/TDO_EXP") (class "Default")
      (node (ref "IC3") (pin "23") (pinfunction "PC6(OC1A/PCINT8)_23") (pintype "bidirectional"))
      (node (ref "SV1") (pin "8") (pinfunction "8_8") (pintype "passive"))
    )
    (net (code "81") (name "/TDO_PROM") (class "Default")
      (node (ref "IC1") (pin "17") (pinfunction "TDO_17") (pintype "bidirectional"))
      (node (ref "IC3") (pin "20") (pinfunction "PB6(PCINT6)_20") (pintype "bidirectional"))
      (node (ref "SV1") (pin "10") (pinfunction "10_10") (pintype "passive"))
    )
    (net (code "82") (name "/TMS") (class "Default")
      (node (ref "IC1") (pin "5") (pinfunction "TMS_5") (pintype "bidirectional"))
      (node (ref "IC3") (pin "18") (pinfunction "PB4(T1/PCINT4)_18") (pintype "bidirectional"))
      (node (ref "R3") (pin "2") (pinfunction "2_2") (pintype "passive"))
      (node (ref "SV1") (pin "12") (pinfunction "12_12") (pintype "passive"))
    )
    (net (code "83") (name "/VCC") (class "Default")
      (node (ref "C10") (pin "1") (pinfunction "1_1") (pintype "passive"))
      (node (ref "C11") (pin "1") (pinfunction "1_1") (pintype "passive"))
      (node (ref "C12") (pin "1") (pinfunction "1_1") (pintype "passive"))
      (node (ref "C13") (pin "1") (pinfunction "1_1") (pintype "passive"))
      (node (ref "C14") (pin "1") (pinfunction "1_1") (pintype "passive"))
      (node (ref "C15") (pin "1") (pinfunction "1_1") (pintype "passive"))
      (node (ref "C16") (pin "1") (pinfunction "1_1") (pintype "passive"))
      (node (ref "C17") (pin "1") (pinfunction "1_1") (pintype "passive"))
      (node (ref "C26") (pin "1") (pinfunction "1_1") (pintype "passive"))
      (node (ref "C27") (pin "1") (pinfunction "1_1") (pintype "passive"))
      (node (ref "C29") (pin "1") (pinfunction "1_1") (pintype "passive"))
      (node (ref "C34") (pin "1") (pinfunction "1_1") (pintype "passive"))
      (node (ref "C39") (pin "+") (pinfunction "+_+") (pintype "passive"))
      (node (ref "C6") (pin "1") (pinfunction "1_1") (pintype "passive"))
      (node (ref "C7") (pin "1") (pinfunction "1_1") (pintype "passive"))
      (node (ref "C8") (pin "1") (pinfunction "1_1") (pintype "passive"))
      (node (ref "C9") (pin "1") (pinfunction "1_1") (pintype "passive"))
      (node (ref "IC1") (pin "18") (pinfunction "VCCINT_18") (pintype "bidirectional"))
      (node (ref "IC1") (pin "19") (pinfunction "VCCO_19") (pintype "bidirectional"))
      (node (ref "IC1") (pin "20") (pinfunction "VCCJ_20") (pintype "bidirectional"))
      (node (ref "IC2") (pin "8") (pinfunction "VCC_8") (pintype "power_in"))
      (node (ref "IC3") (pin "31") (pinfunction "UVCC_31") (pintype "bidirectional"))
      (node (ref "IC3") (pin "32") (pinfunction "AVCC_32") (pintype "bidirectional"))
      (node (ref "IC3") (pin "4") (pinfunction "VCC_4") (pintype "bidirectional"))
      (node (ref "Q5") (pin "3") (pinfunction "C_3") (pintype "passive"))
      (node (ref "Q6") (pin "3") (pinfunction "C_3") (pintype "passive"))
      (node (ref "Q7") (pin "3") (pinfunction "C_3") (pintype "passive"))
      (node (ref "Q8") (pin "3") (pinfunction "C_3") (pintype "passive"))
      (node (ref "R11") (pin "1") (pinfunction "1_1") (pintype "passive"))
      (node (ref "R22") (pin "1") (pinfunction "1_1") (pintype "passive"))
      (node (ref "R35") (pin "2") (pinfunction "2_2") (pintype "passive"))
      (node (ref "R36") (pin "2") (pinfunction "2_2") (pintype "passive"))
      (node (ref "R37") (pin "2") (pinfunction "2_2") (pintype "passive"))
      (node (ref "R38") (pin "2") (pinfunction "2_2") (pintype "passive"))
      (node (ref "R39") (pin "2") (pinfunction "2_2") (pintype "passive"))
      (node (ref "R4") (pin "2") (pinfunction "2_2") (pintype "passive"))
      (node (ref "R40") (pin "1") (pinfunction "1_1") (pintype "passive"))
      (node (ref "R41") (pin "1") (pinfunction "1_1") (pintype "passive"))
      (node (ref "R42") (pin "1") (pinfunction "1_1") (pintype "passive"))
      (node (ref "R43") (pin "1") (pinfunction "1_1") (pintype "passive"))
      (node (ref "R44") (pin "1") (pinfunction "1_1") (pintype "passive"))
      (node (ref "R45") (pin "1") (pinfunction "1_1") (pintype "passive"))
      (node (ref "R46") (pin "2") (pinfunction "2_2") (pintype "passive"))
      (node (ref "R55") (pin "1") (pinfunction "1_1") (pintype "passive"))
      (node (ref "R56") (pin "1") (pinfunction "1_1") (pintype "passive"))
      (node (ref "R6") (pin "2") (pinfunction "2_2") (pintype "passive"))
      (node (ref "REG3.3") (pin "4") (pinfunction "VOUT1_4") (pintype "bidirectional"))
      (node (ref "SV1") (pin "3") (pinfunction "3_3") (pintype "passive"))
      (node (ref "SV1") (pin "4") (pinfunction "4_4") (pintype "passive"))
      (node (ref "SV2") (pin "4") (pinfunction "4_4") (pintype "passive"))
      (node (ref "SV2") (pin "6") (pinfunction "6_6") (pintype "passive"))
      (node (ref "SV3") (pin "1") (pinfunction "1_1") (pintype "passive"))
      (node (ref "SV5") (pin "7") (pinfunction "7_7") (pintype "passive"))
      (node (ref "SV5") (pin "8") (pinfunction "8_8") (pintype "passive"))
      (node (ref "T1") (pin "3") (pinfunction "G_3") (pintype "passive"))
      (node (ref "T2") (pin "3") (pinfunction "C_3") (pintype "passive"))
      (node (ref "T3") (pin "3") (pinfunction "G_3") (pintype "passive"))
      (node (ref "U$2") (pin "VDD") (pinfunction "VDD_VDD") (pintype "power_in"))
      (node (ref "U$3") (pin "4") (pinfunction "VDD_4") (pintype "power_in"))
      (node (ref "U$6") (pin "P8") (pinfunction "VCC_P8") (pintype "bidirectional"))
      (node (ref "U1") (pin "P106") (pinfunction "VCCO_RIGHT2_P106") (pintype "passive"))
      (node (ref "U1") (pin "P115") (pinfunction "VCCO_TOP0_P115") (pintype "passive"))
      (node (ref "U1") (pin "P126") (pinfunction "VCCO_TOP1_P126") (pintype "passive"))
      (node (ref "U1") (pin "P138") (pinfunction "VCCO_TOP2_P138") (pintype "passive"))
      (node (ref "U1") (pin "P19") (pinfunction "VCCO_LEFT1_P19") (pintype "passive"))
      (node (ref "U1") (pin "P3") (pinfunction "VCCO_LEFT0_P3") (pintype "passive"))
      (node (ref "U1") (pin "P34") (pinfunction "VCCO_LEFT2_P34") (pintype "passive"))
      (node (ref "U1") (pin "P43") (pinfunction "VCCO_BOTTOM0_P43") (pintype "passive"))
      (node (ref "U1") (pin "P54") (pinfunction "VCCO_BOTTOM1_P54") (pintype "passive"))
      (node (ref "U1") (pin "P66") (pinfunction "VCCO_BOTTOM2_P66") (pintype "passive"))
      (node (ref "U1") (pin "P75") (pinfunction "VCCO_RIGHT0_P75") (pintype "passive"))
      (node (ref "U1") (pin "P91") (pinfunction "VCCO_RIGHT1_P91") (pintype "passive"))
    )
    (net (code "84") (name "/VCC5") (class "Default")
      (node (ref "C33") (pin "+") (pinfunction "+_+") (pintype "passive"))
      (node (ref "PWR_HDR") (pin "2") (pinfunction "2_2") (pintype "passive"))
      (node (ref "R5") (pin "2") (pinfunction "2_2") (pintype "passive"))
      (node (ref "R7") (pin "2") (pinfunction "2_2") (pintype "passive"))
      (node (ref "REG1.2") (pin "3") (pinfunction "VCC_3") (pintype "bidirectional"))
      (node (ref "REG2.5") (pin "3") (pinfunction "VCC_3") (pintype "bidirectional"))
      (node (ref "REG3.3") (pin "3") (pinfunction "VCC_3") (pintype "bidirectional"))
      (node (ref "SV5") (pin "10") (pinfunction "10_10") (pintype "passive"))
      (node (ref "SV5") (pin "9") (pinfunction "9_9") (pintype "passive"))
      (node (ref "X3") (pin "5") (pinfunction "5_5") (pintype "passive"))
      (node (ref "X7") (pin "2") (pinfunction "2_2") (pintype "power_in"))
    )
    (net (code "85") (name "/VCCAUX") (class "Default")
      (node (ref "C18") (pin "1") (pinfunction "1_1") (pintype "passive"))
      (node (ref "C19") (pin "1") (pinfunction "1_1") (pintype "passive"))
      (node (ref "C20") (pin "1") (pinfunction "1_1") (pintype "passive"))
      (node (ref "C21") (pin "1") (pinfunction "1_1") (pintype "passive"))
      (node (ref "C40") (pin "+") (pinfunction "+_+") (pintype "passive"))
      (node (ref "R50") (pin "2") (pinfunction "2_2") (pintype "passive"))
      (node (ref "REG2.5") (pin "4") (pinfunction "VOUT1_4") (pintype "bidirectional"))
      (node (ref "SV5") (pin "2") (pinfunction "2_2") (pintype "passive"))
      (node (ref "U1") (pin "P120") (pinfunction "VCCAUX2_P120") (pintype "passive"))
      (node (ref "U1") (pin "P134") (pinfunction "VCCAUX3_P134") (pintype "passive"))
      (node (ref "U1") (pin "P48") (pinfunction "VCCAUX0_P48") (pintype "passive"))
      (node (ref "U1") (pin "P62") (pinfunction "VCCAUX1_P62") (pintype "passive"))
    )
    (net (code "86") (name "/VCCINT") (class "Default")
      (node (ref "C22") (pin "1") (pinfunction "1_1") (pintype "passive"))
      (node (ref "C23") (pin "1") (pinfunction "1_1") (pintype "passive"))
      (node (ref "C24") (pin "1") (pinfunction "1_1") (pintype "passive"))
      (node (ref "C25") (pin "1") (pinfunction "1_1") (pintype "passive"))
      (node (ref "C42") (pin "+") (pinfunction "+_+") (pintype "passive"))
      (node (ref "REG1.2") (pin "4") (pinfunction "VOUT1_4") (pintype "bidirectional"))
      (node (ref "SV5") (pin "1") (pinfunction "1_1") (pintype "passive"))
      (node (ref "U1") (pin "P121") (pinfunction "VCCINT2_P121") (pintype "passive"))
      (node (ref "U1") (pin "P133") (pinfunction "VCCINT3_P133") (pintype "passive"))
      (node (ref "U1") (pin "P49") (pinfunction "VCCINT0_P49") (pintype "passive"))
      (node (ref "U1") (pin "P61") (pinfunction "VCCINT1_P61") (pintype "passive"))
    )
    (net (code "87") (name "/X3") (class "Default")
      (node (ref "SV2") (pin "5") (pinfunction "5_5") (pintype "passive"))
      (node (ref "U1") (pin "P76") (pinfunction "IO_P76") (pintype "bidirectional"))
    )
    (net (code "88") (name "/X4") (class "Default")
      (node (ref "SV2") (pin "3") (pinfunction "3_3") (pintype "passive"))
      (node (ref "U1") (pin "P77") (pinfunction "IO_L20P_3_P77") (pintype "bidirectional"))
    )
    (net (code "89") (name "/X8") (class "Default")
      (node (ref "SV2") (pin "1") (pinfunction "1_1") (pintype "passive"))
      (node (ref "U1") (pin "P74") (pinfunction "IO_L01N_3VRP_3_P74") (pintype "bidirectional"))
    )
    (net (code "90") (name "GND") (class "Default")
      (node (ref "C1") (pin "1") (pinfunction "1_1") (pintype "passive"))
      (node (ref "C10") (pin "2") (pinfunction "2_2") (pintype "passive"))
      (node (ref "C11") (pin "2") (pinfunction "2_2") (pintype "passive"))
      (node (ref "C12") (pin "2") (pinfunction "2_2") (pintype "passive"))
      (node (ref "C13") (pin "2") (pinfunction "2_2") (pintype "passive"))
      (node (ref "C14") (pin "2") (pinfunction "2_2") (pintype "passive"))
      (node (ref "C15") (pin "2") (pinfunction "2_2") (pintype "passive"))
      (node (ref "C16") (pin "2") (pinfunction "2_2") (pintype "passive"))
      (node (ref "C17") (pin "2") (pinfunction "2_2") (pintype "passive"))
      (node (ref "C18") (pin "2") (pinfunction "2_2") (pintype "passive"))
      (node (ref "C19") (pin "2") (pinfunction "2_2") (pintype "passive"))
      (node (ref "C20") (pin "2") (pinfunction "2_2") (pintype "passive"))
      (node (ref "C21") (pin "2") (pinfunction "2_2") (pintype "passive"))
      (node (ref "C22") (pin "2") (pinfunction "2_2") (pintype "passive"))
      (node (ref "C23") (pin "2") (pinfunction "2_2") (pintype "passive"))
      (node (ref "C24") (pin "2") (pinfunction "2_2") (pintype "passive"))
      (node (ref "C25") (pin "2") (pinfunction "2_2") (pintype "passive"))
      (node (ref "C26") (pin "2") (pinfunction "2_2") (pintype "passive"))
      (node (ref "C27") (pin "2") (pinfunction "2_2") (pintype "passive"))
      (node (ref "C29") (pin "2") (pinfunction "2_2") (pintype "passive"))
      (node (ref "C33") (pin "-") (pinfunction "-_-") (pintype "passive"))
      (node (ref "C34") (pin "2") (pinfunction "2_2") (pintype "passive"))
      (node (ref "C37") (pin "1") (pinfunction "1_1") (pintype "passive"))
      (node (ref "C38") (pin "1") (pinfunction "1_1") (pintype "passive"))
      (node (ref "C39") (pin "-") (pinfunction "-_-") (pintype "passive"))
      (node (ref "C40") (pin "-") (pinfunction "-_-") (pintype "passive"))
      (node (ref "C41") (pin "2") (pinfunction "2_2") (pintype "passive"))
      (node (ref "C42") (pin "-") (pinfunction "-_-") (pintype "passive"))
      (node (ref "C5") (pin "1") (pinfunction "1_1") (pintype "passive"))
      (node (ref "C6") (pin "2") (pinfunction "2_2") (pintype "passive"))
      (node (ref "C7") (pin "2") (pinfunction "2_2") (pintype "passive"))
      (node (ref "C8") (pin "2") (pinfunction "2_2") (pintype "passive"))
      (node (ref "C9") (pin "2") (pinfunction "2_2") (pintype "passive"))
      (node (ref "IC1") (pin "11") (pinfunction "GND_11") (pintype "bidirectional"))
      (node (ref "IC2") (pin "4") (pinfunction "GND_4") (pintype "power_in"))
      (node (ref "IC3") (pin "3") (pinfunction "GND_3") (pintype "bidirectional"))
      (node (ref "LED1") (pin "C") (pinfunction "C_C") (pintype "passive"))
      (node (ref "PWR_HDR") (pin "1") (pinfunction "1_1") (pintype "passive"))
      (node (ref "R17") (pin "1") (pinfunction "1_1") (pintype "passive"))
      (node (ref "R19") (pin "1") (pinfunction "1_1") (pintype "passive"))
      (node (ref "R21") (pin "1") (pinfunction "1_1") (pintype "passive"))
      (node (ref "REG1.2") (pin "1") (pinfunction "GND_1") (pintype "bidirectional"))
      (node (ref "REG2.5") (pin "1") (pinfunction "GND_1") (pintype "bidirectional"))
      (node (ref "REG3.3") (pin "1") (pinfunction "GND_1") (pintype "bidirectional"))
      (node (ref "SV1") (pin "5") (pinfunction "5_5") (pintype "passive"))
      (node (ref "SV1") (pin "6") (pinfunction "6_6") (pintype "passive"))
      (node (ref "SV2") (pin "2") (pinfunction "2_2") (pintype "passive"))
      (node (ref "SV3") (pin "2") (pinfunction "2_2") (pintype "passive"))
      (node (ref "SV5") (pin "3") (pinfunction "3_3") (pintype "passive"))
      (node (ref "U$1") (pin "GND") (pinfunction "GND_GND") (pintype "bidirectional"))
      (node (ref "U$2") (pin "GND") (pinfunction "GND_GND") (pintype "power_in"))
      (node (ref "U$3") (pin "3") (pinfunction "VSS1_3") (pintype "power_in"))
      (node (ref "U$3") (pin "6") (pinfunction "VSS2_6") (pintype "power_in"))
      (node (ref "U$3") (pin "MT1") (pinfunction "COMMON_SW_MT1") (pintype "passive"))
      (node (ref "U$3") (pin "MT3") (pinfunction "GND_MT3") (pintype "power_in"))
      (node (ref "U$6") (pin "P24") (pinfunction "VSS_P24") (pintype "bidirectional"))
      (node (ref "U$6") (pin "P30") (pinfunction "CE_P30") (pintype "bidirectional"))
      (node (ref "U$7") (pin "GND") (pinfunction "GND_GND") (pintype "bidirectional"))
      (node (ref "U$8") (pin "GND") (pinfunction "GND_GND") (pintype "bidirectional"))
      (node (ref "U$9") (pin "GND") (pinfunction "GND_GND") (pintype "bidirectional"))
      (node (ref "U1") (pin "P101") (pinfunction "GND11_P101") (pintype "passive"))
      (node (ref "U1") (pin "P114") (pinfunction "GND12_P114") (pintype "passive"))
      (node (ref "U1") (pin "P117") (pinfunction "GND13_P117") (pintype "passive"))
      (node (ref "U1") (pin "P136") (pinfunction "GND14_P136") (pintype "passive"))
      (node (ref "U1") (pin "P139") (pinfunction "GND15_P139") (pintype "passive"))
      (node (ref "U1") (pin "P16") (pinfunction "GND1_P16") (pintype "passive"))
      (node (ref "U1") (pin "P22") (pinfunction "GND2_P22") (pintype "passive"))
      (node (ref "U1") (pin "P29") (pinfunction "GND3_P29") (pintype "passive"))
      (node (ref "U1") (pin "P37") (pinfunction "M1_P37") (pintype "bidirectional"))
      (node (ref "U1") (pin "P38") (pinfunction "M0_P38") (pintype "bidirectional"))
      (node (ref "U1") (pin "P39") (pinfunction "M2_P39") (pintype "bidirectional"))
      (node (ref "U1") (pin "P42") (pinfunction "GND4_P42") (pintype "passive"))
      (node (ref "U1") (pin "P45") (pinfunction "GND5_P45") (pintype "passive"))
      (node (ref "U1") (pin "P64") (pinfunction "GND6_P64") (pintype "passive"))
      (node (ref "U1") (pin "P67") (pinfunction "GND7_P67") (pintype "passive"))
      (node (ref "U1") (pin "P81") (pinfunction "GND8_P81") (pintype "passive"))
      (node (ref "U1") (pin "P88") (pinfunction "GND9_P88") (pintype "passive"))
      (node (ref "U1") (pin "P9") (pinfunction "GND0_P9") (pintype "passive"))
      (node (ref "U1") (pin "P94") (pinfunction "GND10_P94") (pintype "passive"))
      (node (ref "X1") (pin "13") (pinfunction "13_13") (pintype "passive"))
      (node (ref "X1") (pin "14") (pinfunction "14_14") (pintype "passive"))
      (node (ref "X1") (pin "17") (pinfunction "17_17") (pintype "passive"))
      (node (ref "X1") (pin "18") (pinfunction "18_18") (pintype "passive"))
      (node (ref "X1") (pin "21") (pinfunction "21_21") (pintype "passive"))
      (node (ref "X1") (pin "4") (pinfunction "4_4") (pintype "passive"))
      (node (ref "X1") (pin "5") (pinfunction "5_5") (pintype "passive"))
      (node (ref "X1") (pin "9") (pinfunction "9_9") (pintype "passive"))
      (node (ref "X3") (pin "3") (pinfunction "3_3") (pintype "passive"))
      (node (ref "X3") (pin "SH1") (pinfunction "PE1_SH1") (pintype "power_in"))
      (node (ref "X3") (pin "SH2") (pinfunction "PE2_SH2") (pintype "power_in"))
      (node (ref "X3") (pin "SH3") (pinfunction "PE3_SH3") (pintype "power_in"))
      (node (ref "X4") (pin "8") (pinfunction "F_8") (pintype "passive"))
      (node (ref "X4") (pin "G1") (pinfunction "G1_G1") (pintype "passive"))
      (node (ref "X5") (pin "8") (pinfunction "F_8") (pintype "passive"))
      (node (ref "X5") (pin "G1") (pinfunction "G1_G1") (pintype "passive"))
      (node (ref "X7") (pin "3") (pinfunction "3_3") (pintype "power_in"))
      (node (ref "X8") (pin "1") (pinfunction "1_1") (pintype "passive"))
    )
    (net (code "91") (name "Net-(C1-Pad2)") (class "Default")
      (node (ref "C1") (pin "2") (pinfunction "2_2") (pintype "passive"))
      (node (ref "R23") (pin "2") (pinfunction "2_2") (pintype "passive"))
      (node (ref "R48") (pin "1") (pinfunction "1_1") (pintype "passive"))
    )
    (net (code "92") (name "Net-(C2-Pad1)") (class "Default")
      (node (ref "C2") (pin "1") (pinfunction "1_1") (pintype "passive"))
      (node (ref "R17") (pin "2") (pinfunction "2_2") (pintype "passive"))
      (node (ref "X8") (pin "2") (pinfunction "2_2") (pintype "passive"))
      (node (ref "X8") (pin "3") (pinfunction "3_3") (pintype "passive"))
      (node (ref "X8") (pin "4") (pinfunction "4_4") (pintype "passive"))
      (node (ref "X8") (pin "5") (pinfunction "5_5") (pintype "passive"))
    )
    (net (code "93") (name "Net-(C3-Pad1)") (class "Default")
      (node (ref "C3") (pin "1") (pinfunction "1_1") (pintype "passive"))
      (node (ref "R48") (pin "2") (pinfunction "2_2") (pintype "passive"))
    )
    (net (code "94") (name "Net-(C4-Pad1)") (class "Default")
      (node (ref "C4") (pin "1") (pinfunction "1_1") (pintype "passive"))
      (node (ref "R49") (pin "2") (pinfunction "2_2") (pintype "passive"))
    )
    (net (code "95") (name "Net-(C5-Pad2)") (class "Default")
      (node (ref "C5") (pin "2") (pinfunction "2_2") (pintype "passive"))
      (node (ref "R34") (pin "2") (pinfunction "2_2") (pintype "passive"))
      (node (ref "R49") (pin "1") (pinfunction "1_1") (pintype "passive"))
    )
    (net (code "96") (name "Net-(C38-Pad2)") (class "Default")
      (node (ref "C38") (pin "2") (pinfunction "2_2") (pintype "passive"))
      (node (ref "JP2") (pin "1") (pinfunction "1_1") (pintype "passive"))
      (node (ref "Q1") (pin "2") (pinfunction "2_2") (pintype "passive"))
    )
    (net (code "97") (name "Net-(IC1-CLK)") (class "Default")
      (node (ref "IC1") (pin "3") (pinfunction "CLK_3") (pintype "bidirectional"))
      (node (ref "U1") (pin "P72") (pinfunction "CCLK_P72") (pintype "bidirectional"))
    )
    (net (code "98") (name "Net-(IC1-TDI)") (class "Default")
      (node (ref "IC1") (pin "4") (pinfunction "TDI_4") (pintype "bidirectional"))
      (node (ref "U1") (pin "P109") (pinfunction "TDO_P109") (pintype "bidirectional"))
    )
    (net (code "99") (name "Net-(IC1-{slash}CE)") (class "Default")
      (node (ref "IC1") (pin "10") (pinfunction "/CE_10") (pintype "bidirectional"))
      (node (ref "U1") (pin "P71") (pinfunction "DONE_P71") (pintype "bidirectional"))
    )
    (net (code "100") (name "Net-(IC1-{slash}CF)") (class "Default")
      (node (ref "IC1") (pin "7") (pinfunction "/CF_7") (pintype "bidirectional"))
      (node (ref "U1") (pin "P143") (pinfunction "PROG_B_P143") (pintype "bidirectional"))
    )
    (net (code "101") (name "Net-(IC3-D+)") (class "Default")
      (node (ref "IC3") (pin "29") (pinfunction "D+_29") (pintype "bidirectional"))
      (node (ref "R54") (pin "2") (pinfunction "2_2") (pintype "passive"))
    )
    (net (code "102") (name "Net-(IC3-D-)") (class "Default")
      (node (ref "IC3") (pin "30") (pinfunction "D-_30") (pintype "bidirectional"))
      (node (ref "R53") (pin "2") (pinfunction "2_2") (pintype "passive"))
    )
    (net (code "103") (name "Net-(IC3-UCAP)") (class "Default")
      (node (ref "C41") (pin "1") (pinfunction "1_1") (pintype "passive"))
      (node (ref "IC3") (pin "27") (pinfunction "UCAP_27") (pintype "bidirectional"))
    )
    (net (code "104") (name "Net-(IC3-UGND)") (class "Default")
      (node (ref "IC3") (pin "28") (pinfunction "UGND_28") (pintype "bidirectional"))
      (node (ref "X6") (pin "4") (pinfunction "4_4") (pintype "passive"))
    )
    (net (code "105") (name "Net-(IC3-XTAL1)") (class "Default")
      (node (ref "IC3") (pin "1") (pinfunction "XTAL1_1") (pintype "bidirectional"))
      (node (ref "JP2") (pin "2") (pinfunction "2_2") (pintype "passive"))
    )
    (net (code "106") (name "Net-(IC3-XTAL2{slash}PC0)") (class "Default")
      (node (ref "C37") (pin "2") (pinfunction "2_2") (pintype "passive"))
      (node (ref "IC3") (pin "2") (pinfunction "XTAL2/PC0_2") (pintype "bidirectional"))
      (node (ref "Q1") (pin "1") (pinfunction "1_1") (pintype "passive"))
    )
    (net (code "107") (name "Net-(LED1-PadA)") (class "Default")
      (node (ref "LED1") (pin "A") (pinfunction "A_A") (pintype "passive"))
      (node (ref "R11") (pin "2") (pinfunction "2_2") (pintype "passive"))
    )
    (net (code "108") (name "Net-(Q5-B)") (class "Default")
      (node (ref "Q5") (pin "1") (pinfunction "B_1") (pintype "passive"))
      (node (ref "R8") (pin "2") (pinfunction "2_2") (pintype "passive"))
    )
    (net (code "109") (name "Net-(Q5-E)") (class "Default")
      (node (ref "Q5") (pin "2") (pinfunction "E_2") (pintype "passive"))
      (node (ref "R13") (pin "2") (pinfunction "2_2") (pintype "passive"))
      (node (ref "R14") (pin "2") (pinfunction "2_2") (pintype "passive"))
    )
    (net (code "110") (name "Net-(Q6-B)") (class "Default")
      (node (ref "Q6") (pin "1") (pinfunction "B_1") (pintype "passive"))
      (node (ref "R10") (pin "2") (pinfunction "2_2") (pintype "passive"))
      (node (ref "R9") (pin "2") (pinfunction "2_2") (pintype "passive"))
    )
    (net (code "111") (name "Net-(Q6-E)") (class "Default")
      (node (ref "Q6") (pin "2") (pinfunction "E_2") (pintype "passive"))
      (node (ref "R15") (pin "2") (pinfunction "2_2") (pintype "passive"))
      (node (ref "R16") (pin "2") (pinfunction "2_2") (pintype "passive"))
      (node (ref "R20") (pin "2") (pinfunction "2_2") (pintype "passive"))
    )
    (net (code "112") (name "Net-(Q7-B)") (class "Default")
      (node (ref "Q7") (pin "1") (pinfunction "B_1") (pintype "passive"))
      (node (ref "R29") (pin "2") (pinfunction "2_2") (pintype "passive"))
      (node (ref "R30") (pin "2") (pinfunction "2_2") (pintype "passive"))
    )
    (net (code "113") (name "Net-(Q7-E)") (class "Default")
      (node (ref "Q7") (pin "2") (pinfunction "E_2") (pintype "passive"))
      (node (ref "R31") (pin "2") (pinfunction "2_2") (pintype "passive"))
      (node (ref "R32") (pin "2") (pinfunction "2_2") (pintype "passive"))
      (node (ref "R33") (pin "2") (pinfunction "2_2") (pintype "passive"))
    )
    (net (code "114") (name "Net-(Q8-B)") (class "Default")
      (node (ref "Q8") (pin "1") (pinfunction "B_1") (pintype "passive"))
      (node (ref "R24") (pin "2") (pinfunction "2_2") (pintype "passive"))
      (node (ref "R25") (pin "2") (pinfunction "2_2") (pintype "passive"))
    )
    (net (code "115") (name "Net-(Q8-E)") (class "Default")
      (node (ref "Q8") (pin "2") (pinfunction "E_2") (pintype "passive"))
      (node (ref "R26") (pin "2") (pinfunction "2_2") (pintype "passive"))
      (node (ref "R27") (pin "2") (pinfunction "2_2") (pintype "passive"))
      (node (ref "R28") (pin "2") (pinfunction "2_2") (pintype "passive"))
    )
    (net (code "116") (name "Net-(R18-Pad2)") (class "Default")
      (node (ref "R18") (pin "2") (pinfunction "2_2") (pintype "passive"))
      (node (ref "R22") (pin "2") (pinfunction "2_2") (pintype "passive"))
    )
    (net (code "117") (name "Net-(R53-Pad1)") (class "Default")
      (node (ref "R53") (pin "1") (pinfunction "1_1") (pintype "passive"))
      (node (ref "X6") (pin "2") (pinfunction "2_2") (pintype "passive"))
    )
    (net (code "118") (name "Net-(R54-Pad1)") (class "Default")
      (node (ref "R54") (pin "1") (pinfunction "1_1") (pintype "passive"))
      (node (ref "X6") (pin "3") (pinfunction "3_3") (pintype "passive"))
    )
    (net (code "119") (name "Net-(T2-B)") (class "Default")
      (node (ref "C2") (pin "2") (pinfunction "2_2") (pintype "passive"))
      (node (ref "R18") (pin "1") (pinfunction "1_1") (pintype "passive"))
      (node (ref "R19") (pin "2") (pinfunction "2_2") (pintype "passive"))
      (node (ref "T2") (pin "1") (pinfunction "B_1") (pintype "passive"))
    )
    (net (code "120") (name "Net-(U$6-A0)") (class "Default")
      (node (ref "U$6") (pin "P20") (pinfunction "A0_P20") (pintype "bidirectional"))
      (node (ref "U1") (pin "P24") (pinfunction "IO_L24N_6VREF_6_P24") (pintype "bidirectional"))
    )
    (net (code "121") (name "Net-(U$6-A1)") (class "Default")
      (node (ref "U$6") (pin "P19") (pinfunction "A1_P19") (pintype "bidirectional"))
      (node (ref "U1") (pin "P23") (pinfunction "IO_L24P_6_P23") (pintype "bidirectional"))
    )
    (net (code "122") (name "Net-(U$6-A2)") (class "Default")
      (node (ref "U$6") (pin "P18") (pinfunction "A2_P18") (pintype "bidirectional"))
      (node (ref "U1") (pin "P21") (pinfunction "IO_L40N_6_P21") (pintype "bidirectional"))
    )
    (net (code "123") (name "Net-(U$6-A3)") (class "Default")
      (node (ref "U$6") (pin "P17") (pinfunction "A3_P17") (pintype "bidirectional"))
      (node (ref "U1") (pin "P20") (pinfunction "IO_L40P_6VREF_6_P20") (pintype "bidirectional"))
    )
    (net (code "124") (name "Net-(U$6-A4)") (class "Default")
      (node (ref "U$6") (pin "P16") (pinfunction "A4_P16") (pintype "bidirectional"))
      (node (ref "U1") (pin "P18") (pinfunction "IO_L40N_7VREF_7_P18") (pintype "bidirectional"))
    )
    (net (code "125") (name "Net-(U$6-A5)") (class "Default")
      (node (ref "U$6") (pin "P15") (pinfunction "A5_P15") (pintype "bidirectional"))
      (node (ref "U1") (pin "P17") (pinfunction "IO_L40P_7_P17") (pintype "bidirectional"))
    )
    (net (code "126") (name "Net-(U$6-A6)") (class "Default")
      (node (ref "U$6") (pin "P14") (pinfunction "A6_P14") (pintype "bidirectional"))
      (node (ref "U1") (pin "P15") (pinfunction "IO_L24N_7_P15") (pintype "bidirectional"))
    )
    (net (code "127") (name "Net-(U$6-A7)") (class "Default")
      (node (ref "U$6") (pin "P13") (pinfunction "A7_P13") (pintype "bidirectional"))
      (node (ref "U1") (pin "P14") (pinfunction "IO_L24P_7_P14") (pintype "bidirectional"))
    )
    (net (code "128") (name "Net-(U$6-A8)") (class "Default")
      (node (ref "U$6") (pin "P3") (pinfunction "A8_P3") (pintype "bidirectional"))
      (node (ref "U1") (pin "P4") (pinfunction "IOVREF_7_P4") (pintype "bidirectional"))
    )
    (net (code "129") (name "Net-(U$6-A9)") (class "Default")
      (node (ref "U$6") (pin "P2") (pinfunction "A9_P2") (pintype "bidirectional"))
      (node (ref "U1") (pin "P2") (pinfunction "IO_L01N_7VRP_7_P2") (pintype "bidirectional"))
    )
    (net (code "130") (name "Net-(U$6-A10)") (class "Default")
      (node (ref "U$6") (pin "P31") (pinfunction "A10_P31") (pintype "bidirectional"))
      (node (ref "U1") (pin "P35") (pinfunction "IO_L01P_6VRN_6_P35") (pintype "bidirectional"))
    )
    (net (code "131") (name "Net-(U$6-A11)") (class "Default")
      (node (ref "U$6") (pin "P1") (pinfunction "A11_P1") (pintype "bidirectional"))
      (node (ref "U1") (pin "P1") (pinfunction "IO_L01P_7VRN_7_P1") (pintype "bidirectional"))
    )
    (net (code "132") (name "Net-(U$6-A12)") (class "Default")
      (node (ref "U$6") (pin "P12") (pinfunction "A12_P12") (pintype "bidirectional"))
      (node (ref "U1") (pin "P13") (pinfunction "IO_L23N_7_P13") (pintype "bidirectional"))
    )
    (net (code "133") (name "Net-(U$6-A13)") (class "Default")
      (node (ref "U$6") (pin "P4") (pinfunction "A13_P4") (pintype "bidirectional"))
      (node (ref "U1") (pin "P5") (pinfunction "IO_L20P_7_P5") (pintype "bidirectional"))
    )
    (net (code "134") (name "Net-(U$6-A14)") (class "Default")
      (node (ref "U$6") (pin "P11") (pinfunction "A14_P11") (pintype "bidirectional"))
      (node (ref "U1") (pin "P12") (pinfunction "IO_L23P_7_P12") (pintype "bidirectional"))
    )
    (net (code "135") (name "Net-(U$6-A15)") (class "Default")
      (node (ref "U$6") (pin "P7") (pinfunction "A15_P7") (pintype "bidirectional"))
      (node (ref "U1") (pin "P8") (pinfunction "IO_L21N_7_P8") (pintype "bidirectional"))
    )
    (net (code "136") (name "Net-(U$6-A16)") (class "Default")
      (node (ref "U$6") (pin "P10") (pinfunction "A16_P10") (pintype "bidirectional"))
      (node (ref "U1") (pin "P11") (pinfunction "IO_L22N_7_P11") (pintype "bidirectional"))
    )
    (net (code "137") (name "Net-(U$6-A17)") (class "Default")
      (node (ref "U$6") (pin "P6") (pinfunction "A17_P6") (pintype "bidirectional"))
      (node (ref "U1") (pin "P7") (pinfunction "IO_L21P_7_P7") (pintype "bidirectional"))
    )
    (net (code "138") (name "Net-(U$6-A18)") (class "Default")
      (node (ref "U$6") (pin "P9") (pinfunction "A18_P9") (pintype "bidirectional"))
      (node (ref "U1") (pin "P10") (pinfunction "IO_L22P_7_P10") (pintype "bidirectional"))
    )
    (net (code "139") (name "Net-(U$6-DQ0)") (class "Default")
      (node (ref "U$6") (pin "P21") (pinfunction "DQ0_P21") (pintype "bidirectional"))
      (node (ref "U1") (pin "P25") (pinfunction "IO_L23P_6_P25") (pintype "bidirectional"))
    )
    (net (code "140") (name "Net-(U$6-DQ1)") (class "Default")
      (node (ref "U$6") (pin "P22") (pinfunction "DQ1_P22") (pintype "bidirectional"))
      (node (ref "U1") (pin "P26") (pinfunction "IO_L23N_6_P26") (pintype "bidirectional"))
    )
    (net (code "141") (name "Net-(U$6-DQ2)") (class "Default")
      (node (ref "U$6") (pin "P23") (pinfunction "DQ2_P23") (pintype "bidirectional"))
      (node (ref "U1") (pin "P27") (pinfunction "IO_L22P_6_P27") (pintype "bidirectional"))
    )
    (net (code "142") (name "Net-(U$6-DQ3)") (class "Default")
      (node (ref "U$6") (pin "P25") (pinfunction "DQ3_P25") (pintype "bidirectional"))
      (node (ref "U1") (pin "P28") (pinfunction "IO_L22N_6_P28") (pintype "bidirectional"))
    )
    (net (code "143") (name "Net-(U$6-DQ4)") (class "Default")
      (node (ref "U$6") (pin "P26") (pinfunction "DQ4_P26") (pintype "bidirectional"))
      (node (ref "U1") (pin "P30") (pinfunction "IO_L21P_6_P30") (pintype "bidirectional"))
    )
    (net (code "144") (name "Net-(U$6-DQ5)") (class "Default")
      (node (ref "U$6") (pin "P27") (pinfunction "DQ5_P27") (pintype "bidirectional"))
      (node (ref "U1") (pin "P31") (pinfunction "IO_L21N_6_P31") (pintype "bidirectional"))
    )
    (net (code "145") (name "Net-(U$6-DQ6)") (class "Default")
      (node (ref "U$6") (pin "P28") (pinfunction "DQ6_P28") (pintype "bidirectional"))
      (node (ref "U1") (pin "P32") (pinfunction "IO_L20P_6_P32") (pintype "bidirectional"))
    )
    (net (code "146") (name "Net-(U$6-DQ7)") (class "Default")
      (node (ref "U$6") (pin "P29") (pinfunction "DQ7_P29") (pintype "bidirectional"))
      (node (ref "U1") (pin "P33") (pinfunction "IO_L20N_6_P33") (pintype "bidirectional"))
    )
    (net (code "147") (name "Net-(U$6-OE)") (class "Default")
      (node (ref "U$6") (pin "P32") (pinfunction "OE_P32") (pintype "bidirectional"))
      (node (ref "U1") (pin "P36") (pinfunction "IO_L01N_6VRP_6_P36") (pintype "bidirectional"))
    )
    (net (code "148") (name "Net-(U$6-WE)") (class "Default")
      (node (ref "U$6") (pin "P5") (pinfunction "WE_P5") (pintype "bidirectional"))
      (node (ref "U1") (pin "P6") (pinfunction "IO_L20N_7_P6") (pintype "bidirectional"))
    )
    (net (code "149") (name "Net-(U1A-IO_L27N_0)") (class "Default")
      (node (ref "SV3") (pin "3") (pinfunction "3_3") (pintype "passive"))
      (node (ref "U1") (pin "P137") (pinfunction "IO_L27N_0_P137") (pintype "bidirectional"))
    )
    (net (code "150") (name "Net-(U1A-IO_L27P_0)") (class "Default")
      (node (ref "SV3") (pin "4") (pinfunction "4_4") (pintype "passive"))
      (node (ref "U1") (pin "P135") (pinfunction "IO_L27P_0_P135") (pintype "bidirectional"))
    )
    (net (code "151") (name "Net-(U1A-IO_L30N_0)") (class "Default")
      (node (ref "SV3") (pin "5") (pinfunction "5_5") (pintype "passive"))
      (node (ref "U1") (pin "P132") (pinfunction "IO_L30N_0_P132") (pintype "bidirectional"))
    )
    (net (code "152") (name "Net-(U1A-IO_L31N_0)") (class "Default")
      (node (ref "SV3") (pin "6") (pinfunction "6_6") (pintype "passive"))
      (node (ref "U1") (pin "P130") (pinfunction "IO_L31N_0_P130") (pintype "bidirectional"))
    )
    (net (code "153") (name "Net-(U1A-IO_L31P_0VREF_0)") (class "Default")
      (node (ref "SV3") (pin "7") (pinfunction "7_7") (pintype "passive"))
      (node (ref "U1") (pin "P129") (pinfunction "IO_L31P_0VREF_0_P129") (pintype "bidirectional"))
    )
    (net (code "154") (name "Net-(U1A-IO_L32N_0GCLK7)") (class "Default")
      (node (ref "SV3") (pin "9") (pinfunction "9_9") (pintype "passive"))
      (node (ref "U1") (pin "P128") (pinfunction "IO_L32N_0GCLK7_P128") (pintype "bidirectional"))
    )
    (net (code "155") (name "Net-(U1A-IO_L32P_0GCLK6)") (class "Default")
      (node (ref "SV3") (pin "8") (pinfunction "8_8") (pintype "passive"))
      (node (ref "U1") (pin "P127") (pinfunction "IO_L32P_0GCLK6_P127") (pintype "bidirectional"))
    )
    (net (code "156") (name "Net-(U1C-IO_L31N_1VREF_1)") (class "Default")
      (node (ref "SV3") (pin "10") (pinfunction "10_10") (pintype "passive"))
      (node (ref "U1") (pin "P123") (pinfunction "IO_L31N_1VREF_1_P123") (pintype "bidirectional"))
    )
    (net (code "157") (name "Net-(U1N-TCK)") (class "Default")
      (node (ref "R2") (pin "1") (pinfunction "1_1") (pintype "passive"))
      (node (ref "U1") (pin "P110") (pinfunction "TCK_P110") (pintype "bidirectional"))
    )
    (net (code "158") (name "Net-(U1N-TDI)") (class "Default")
      (node (ref "R1") (pin "1") (pinfunction "1_1") (pintype "passive"))
      (node (ref "U1") (pin "P144") (pinfunction "TDI_P144") (pintype "bidirectional"))
    )
    (net (code "159") (name "Net-(U1N-TMS)") (class "Default")
      (node (ref "R3") (pin "1") (pinfunction "1_1") (pintype "passive"))
      (node (ref "U1") (pin "P111") (pinfunction "TMS_P111") (pintype "bidirectional"))
    )
    (net (code "160") (name "unconnected-(IC1-NC.1-Pad2)") (class "Default")
      (node (ref "IC1") (pin "2") (pinfunction "NC.1_2") (pintype "bidirectional"))
    )
    (net (code "161") (name "unconnected-(IC1-NC.2-Pad9)") (class "Default")
      (node (ref "IC1") (pin "9") (pinfunction "NC.2_9") (pintype "bidirectional"))
    )
    (net (code "162") (name "unconnected-(IC1-NC.3-Pad12)") (class "Default")
      (node (ref "IC1") (pin "12") (pinfunction "NC.3_12") (pintype "bidirectional"))
    )
    (net (code "163") (name "unconnected-(IC1-NC.4-Pad14)") (class "Default")
      (node (ref "IC1") (pin "14") (pinfunction "NC.4_14") (pintype "bidirectional"))
    )
    (net (code "164") (name "unconnected-(IC1-NC.5-Pad15)") (class "Default")
      (node (ref "IC1") (pin "15") (pinfunction "NC.5_15") (pintype "bidirectional"))
    )
    (net (code "165") (name "unconnected-(IC1-NC.6-Pad16)") (class "Default")
      (node (ref "IC1") (pin "16") (pinfunction "NC.6_16") (pintype "bidirectional"))
    )
    (net (code "166") (name "unconnected-(IC1-{slash}CEO-Pad13)") (class "Default")
      (node (ref "IC1") (pin "13") (pinfunction "/CEO_13") (pintype "bidirectional"))
    )
    (net (code "167") (name "unconnected-(REG1.2-VOUT2-Pad2)") (class "Default")
      (node (ref "REG1.2") (pin "2") (pinfunction "VOUT2_2") (pintype "bidirectional"))
    )
    (net (code "168") (name "unconnected-(REG2.5-VOUT2-Pad2)") (class "Default")
      (node (ref "REG2.5") (pin "2") (pinfunction "VOUT2_2") (pintype "bidirectional"))
    )
    (net (code "169") (name "unconnected-(REG3.3-VOUT2-Pad2)") (class "Default")
      (node (ref "REG3.3") (pin "2") (pinfunction "VOUT2_2") (pintype "bidirectional"))
    )
    (net (code "170") (name "unconnected-(U$2-TRI-PadENA)") (class "Default")
      (node (ref "U$2") (pin "ENA") (pinfunction "TRI_ENA") (pintype "input"))
    )
    (net (code "171") (name "unconnected-(U$3-CARD_DETECT-PadCD)") (class "Default")
      (node (ref "U$3") (pin "CD") (pinfunction "CARD_DETECT_CD") (pintype "passive"))
    )
    (net (code "172") (name "unconnected-(U$3-DAT1-Pad8)") (class "Default")
      (node (ref "U$3") (pin "8") (pinfunction "DAT1_8") (pintype "bidirectional"))
    )
    (net (code "173") (name "unconnected-(U$3-DAT2-Pad9)") (class "Default")
      (node (ref "U$3") (pin "9") (pinfunction "DAT2_9") (pintype "bidirectional"))
    )
    (net (code "174") (name "unconnected-(U$3-WRITE_PROTECT-PadWP)") (class "Default")
      (node (ref "U$3") (pin "WP") (pinfunction "WRITE_PROTECT_WP") (pintype "passive"))
    )
    (net (code "175") (name "unconnected-(U1N-HSWAP_EN-PadP142)") (class "Default")
      (node (ref "U1") (pin "P142") (pinfunction "HSWAP_EN_P142") (pintype "bidirectional"))
    )
    (net (code "176") (name "unconnected-(X1-Pad10)") (class "Default")
      (node (ref "X1") (pin "10") (pinfunction "10_10") (pintype "passive"))
    )
    (net (code "177") (name "unconnected-(X1-Pad12)") (class "Default")
      (node (ref "X1") (pin "12") (pinfunction "12_12") (pintype "passive"))
    )
    (net (code "178") (name "unconnected-(X3-Pad2)") (class "Default")
      (node (ref "X3") (pin "2") (pinfunction "2_2") (pintype "passive"))
    )
    (net (code "179") (name "unconnected-(X3-Pad8)") (class "Default")
      (node (ref "X3") (pin "8") (pinfunction "8_8") (pintype "passive"))
    )
    (net (code "180") (name "unconnected-(X4-PadG2)") (class "Default")
      (node (ref "X4") (pin "G2") (pinfunction "G2_G2") (pintype "passive"))
    )
    (net (code "181") (name "unconnected-(X5-PadG2)") (class "Default")
      (node (ref "X5") (pin "G2") (pinfunction "G2_G2") (pintype "passive"))
    )
    (net (code "182") (name "unconnected-(X6-Pad1)") (class "Default")
      (node (ref "X6") (pin "1") (pinfunction "1_1") (pintype "passive"))
    )
  )
)
